# Mainboard.net
KiCad netlist of a schematic drawn in EAGLE
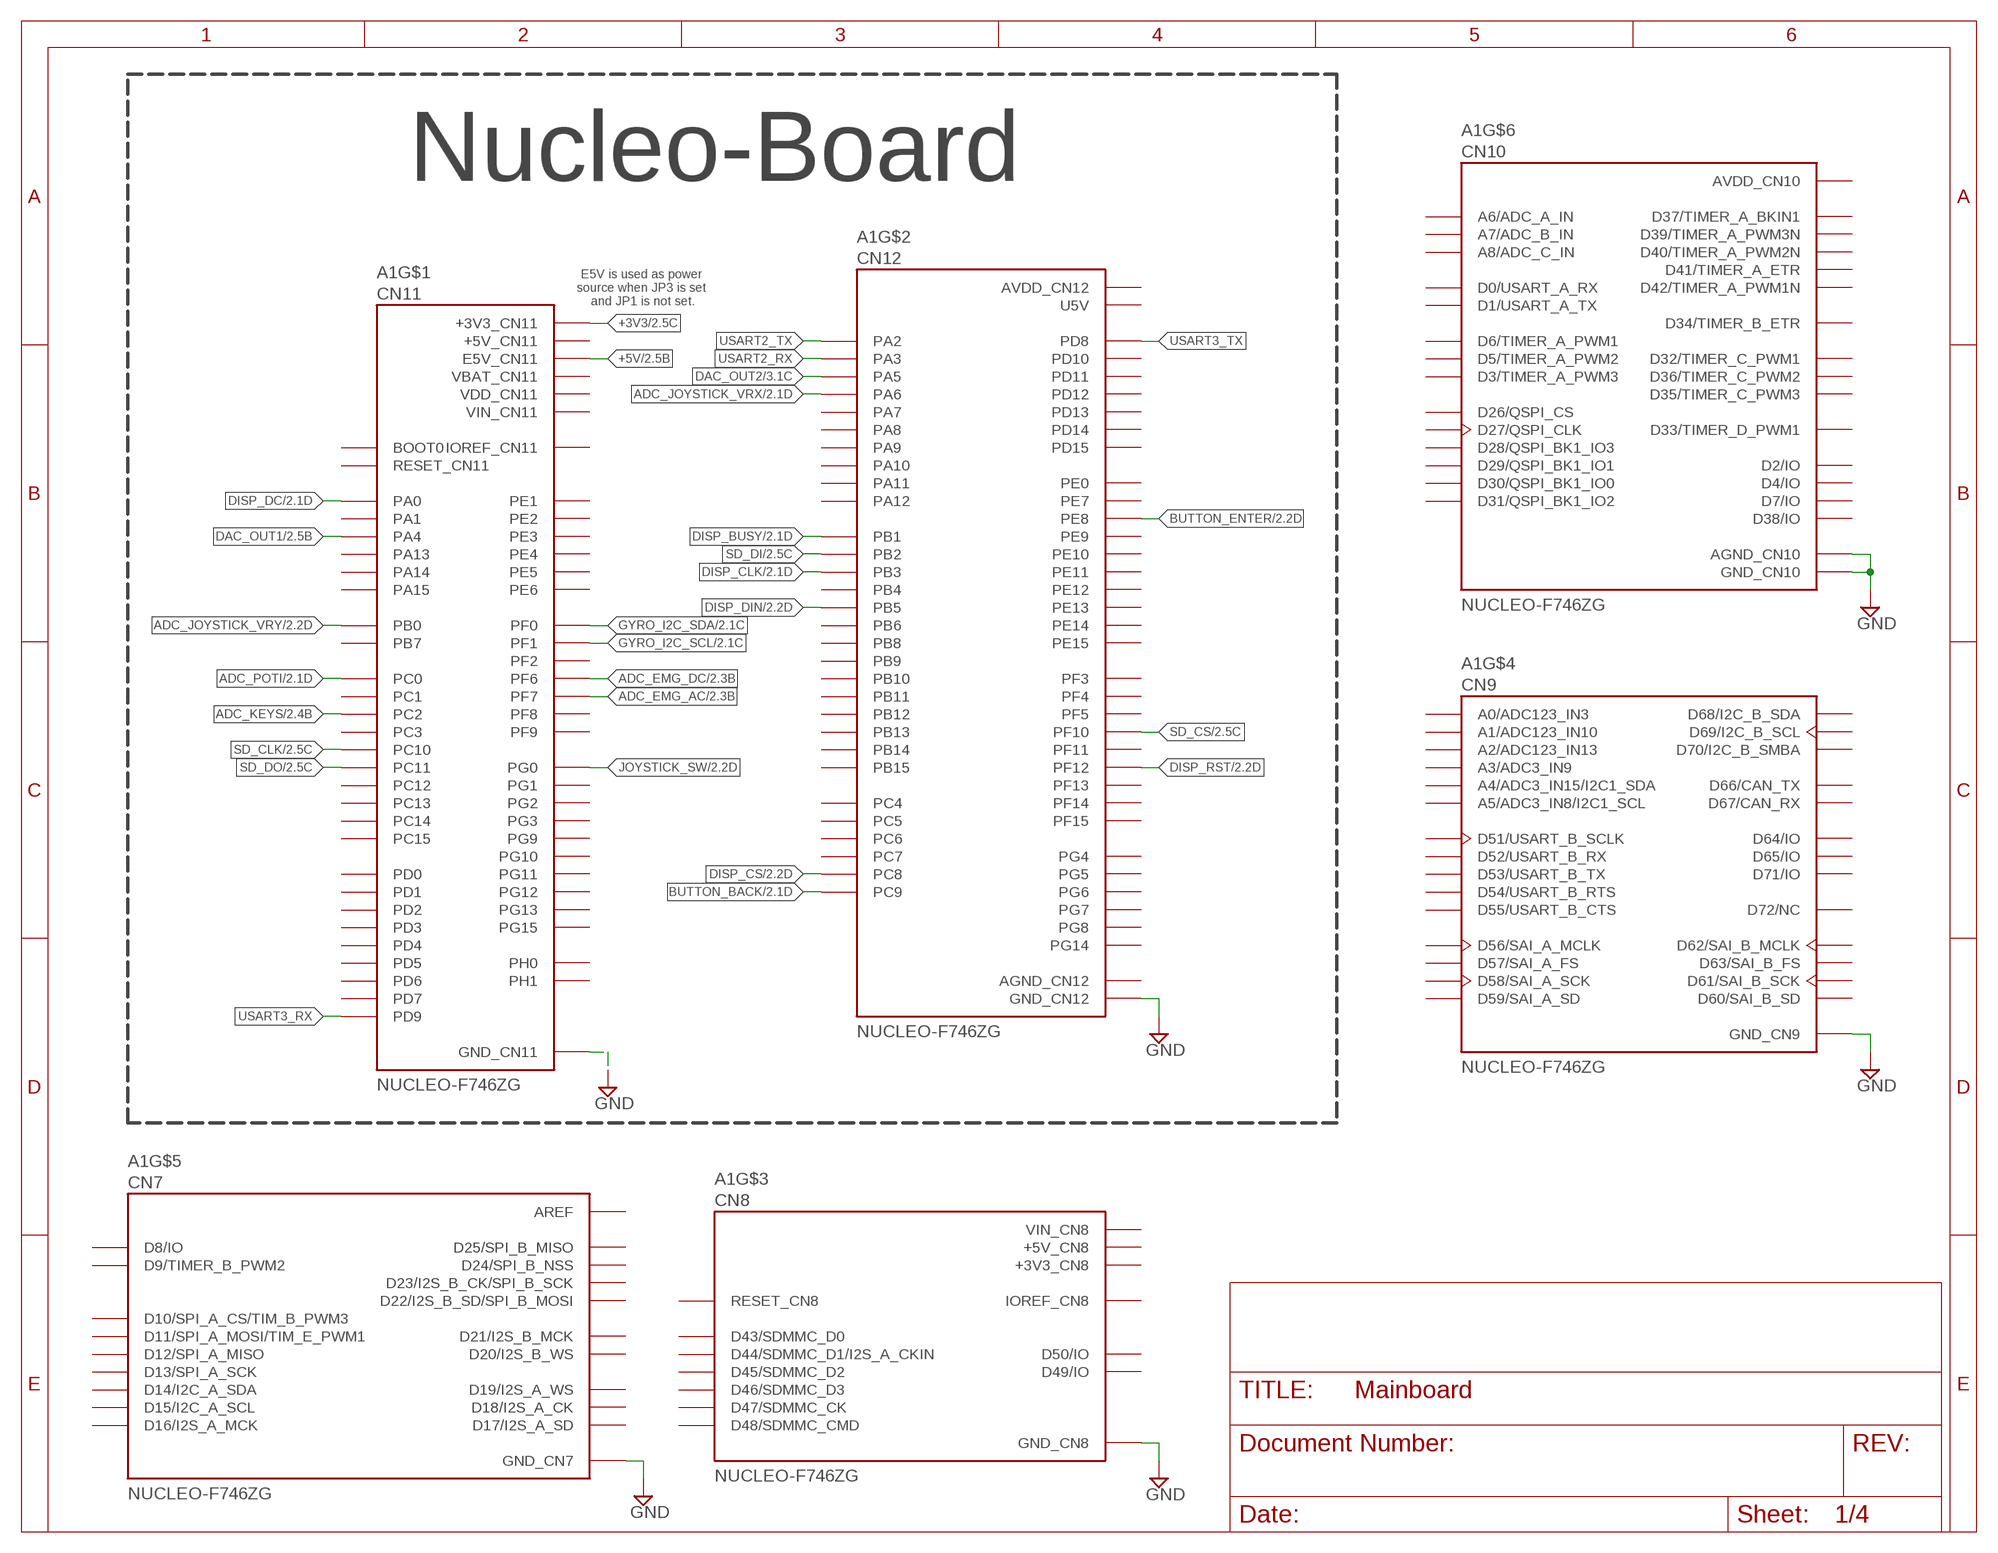
[diagram p0: schematic, sheet 1]
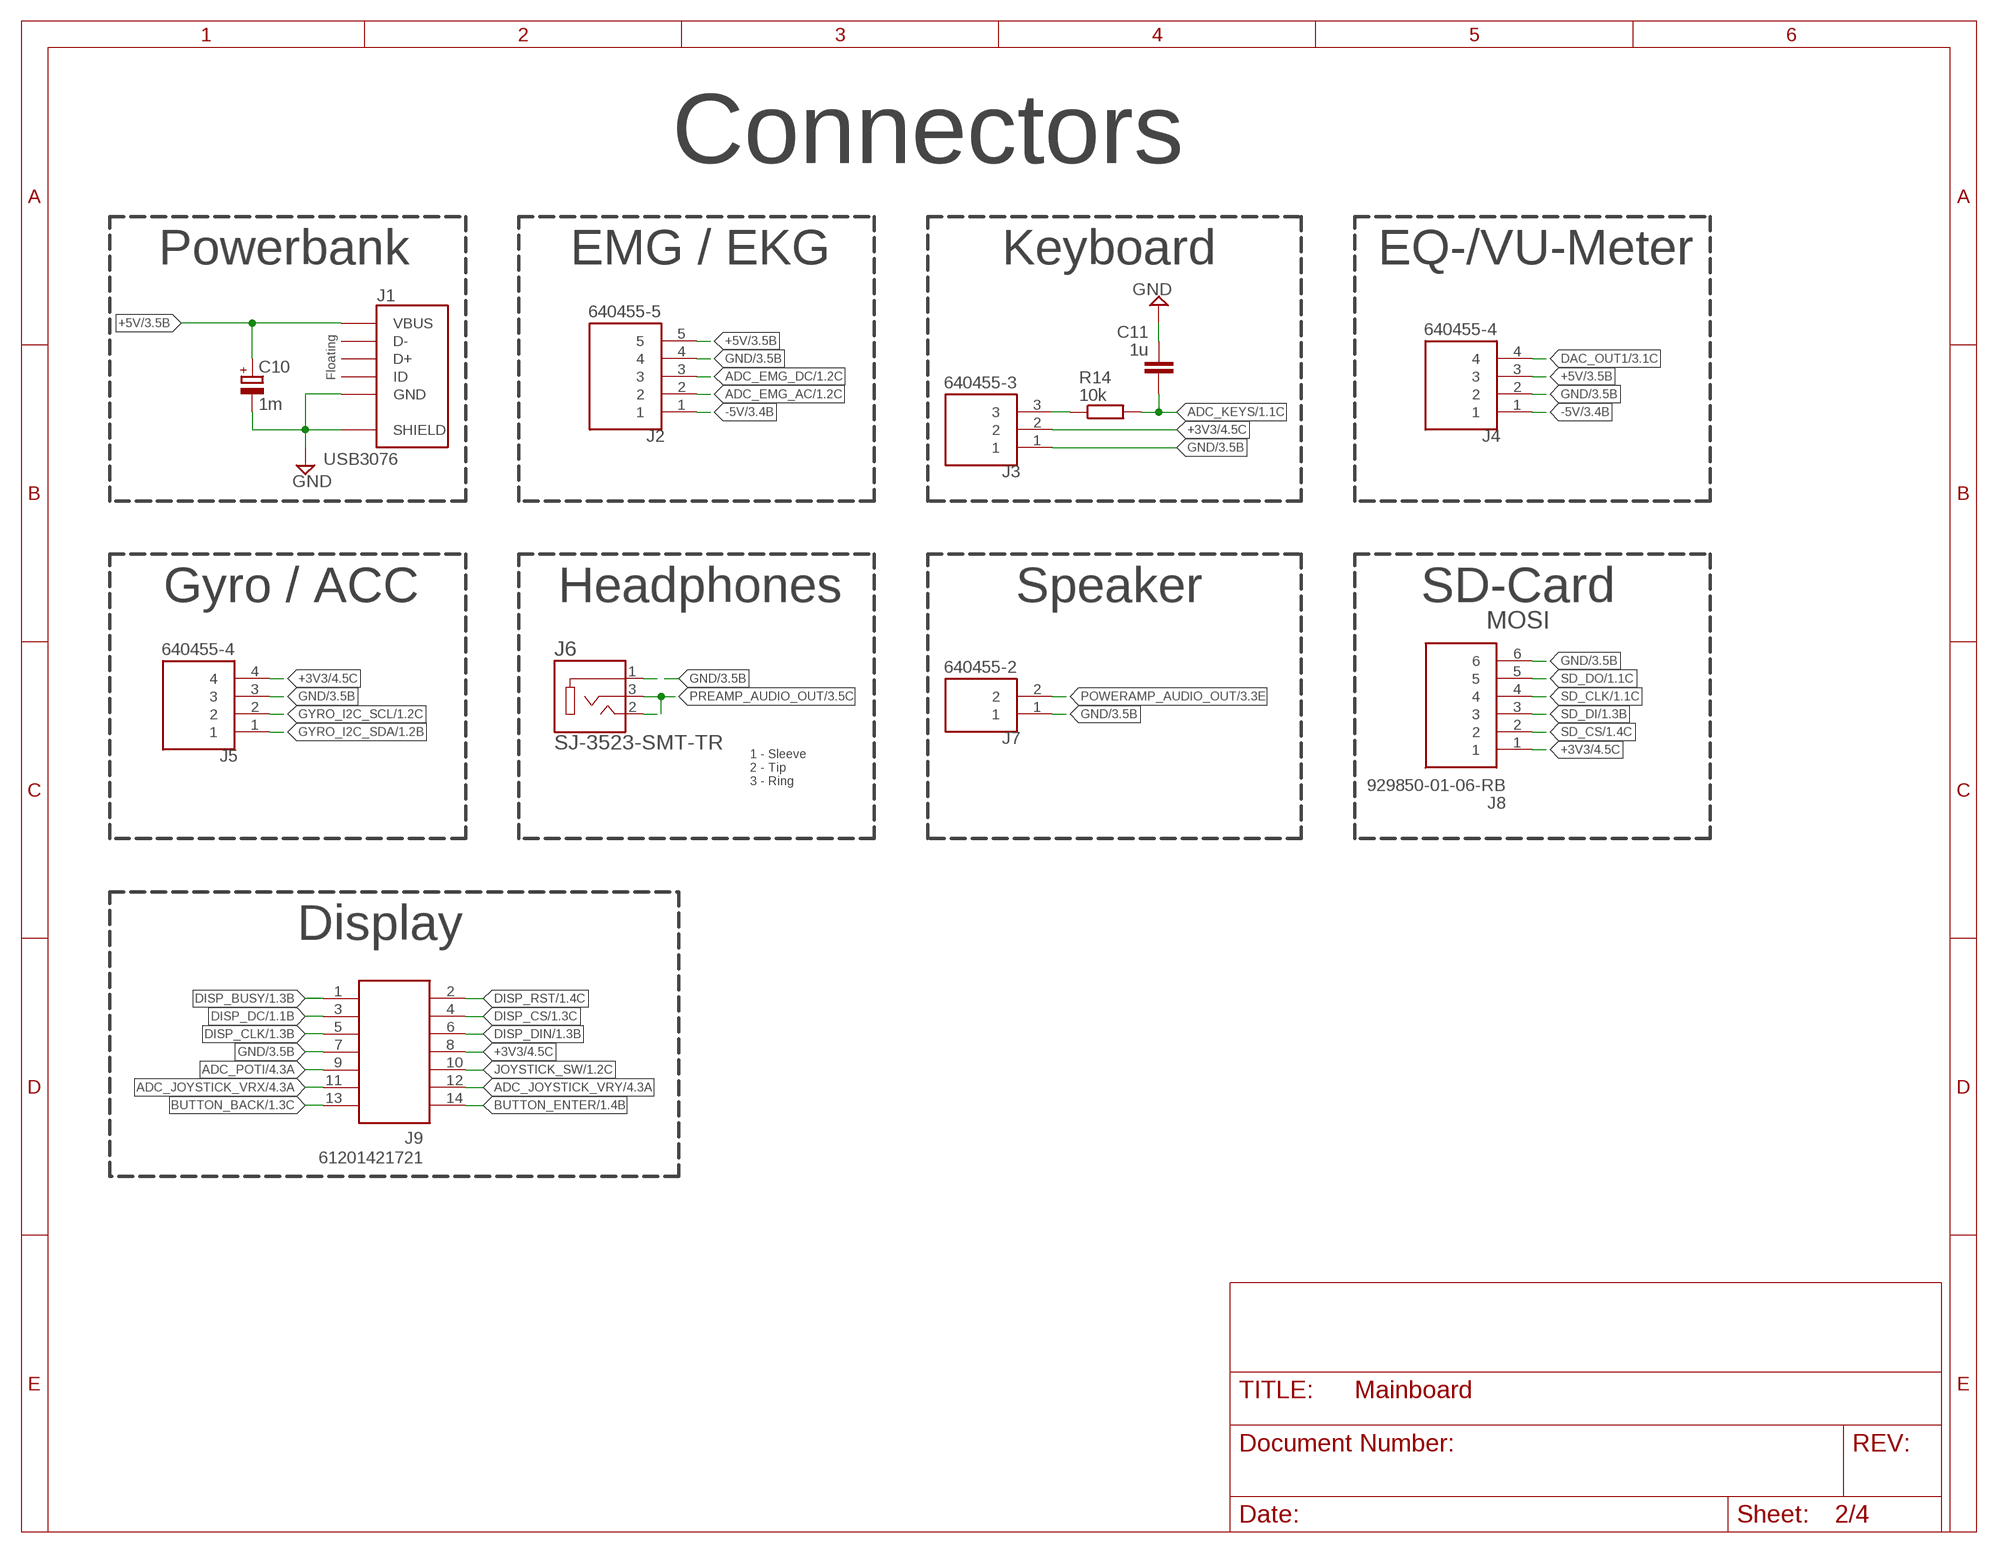
[diagram p1: schematic, sheet 2]
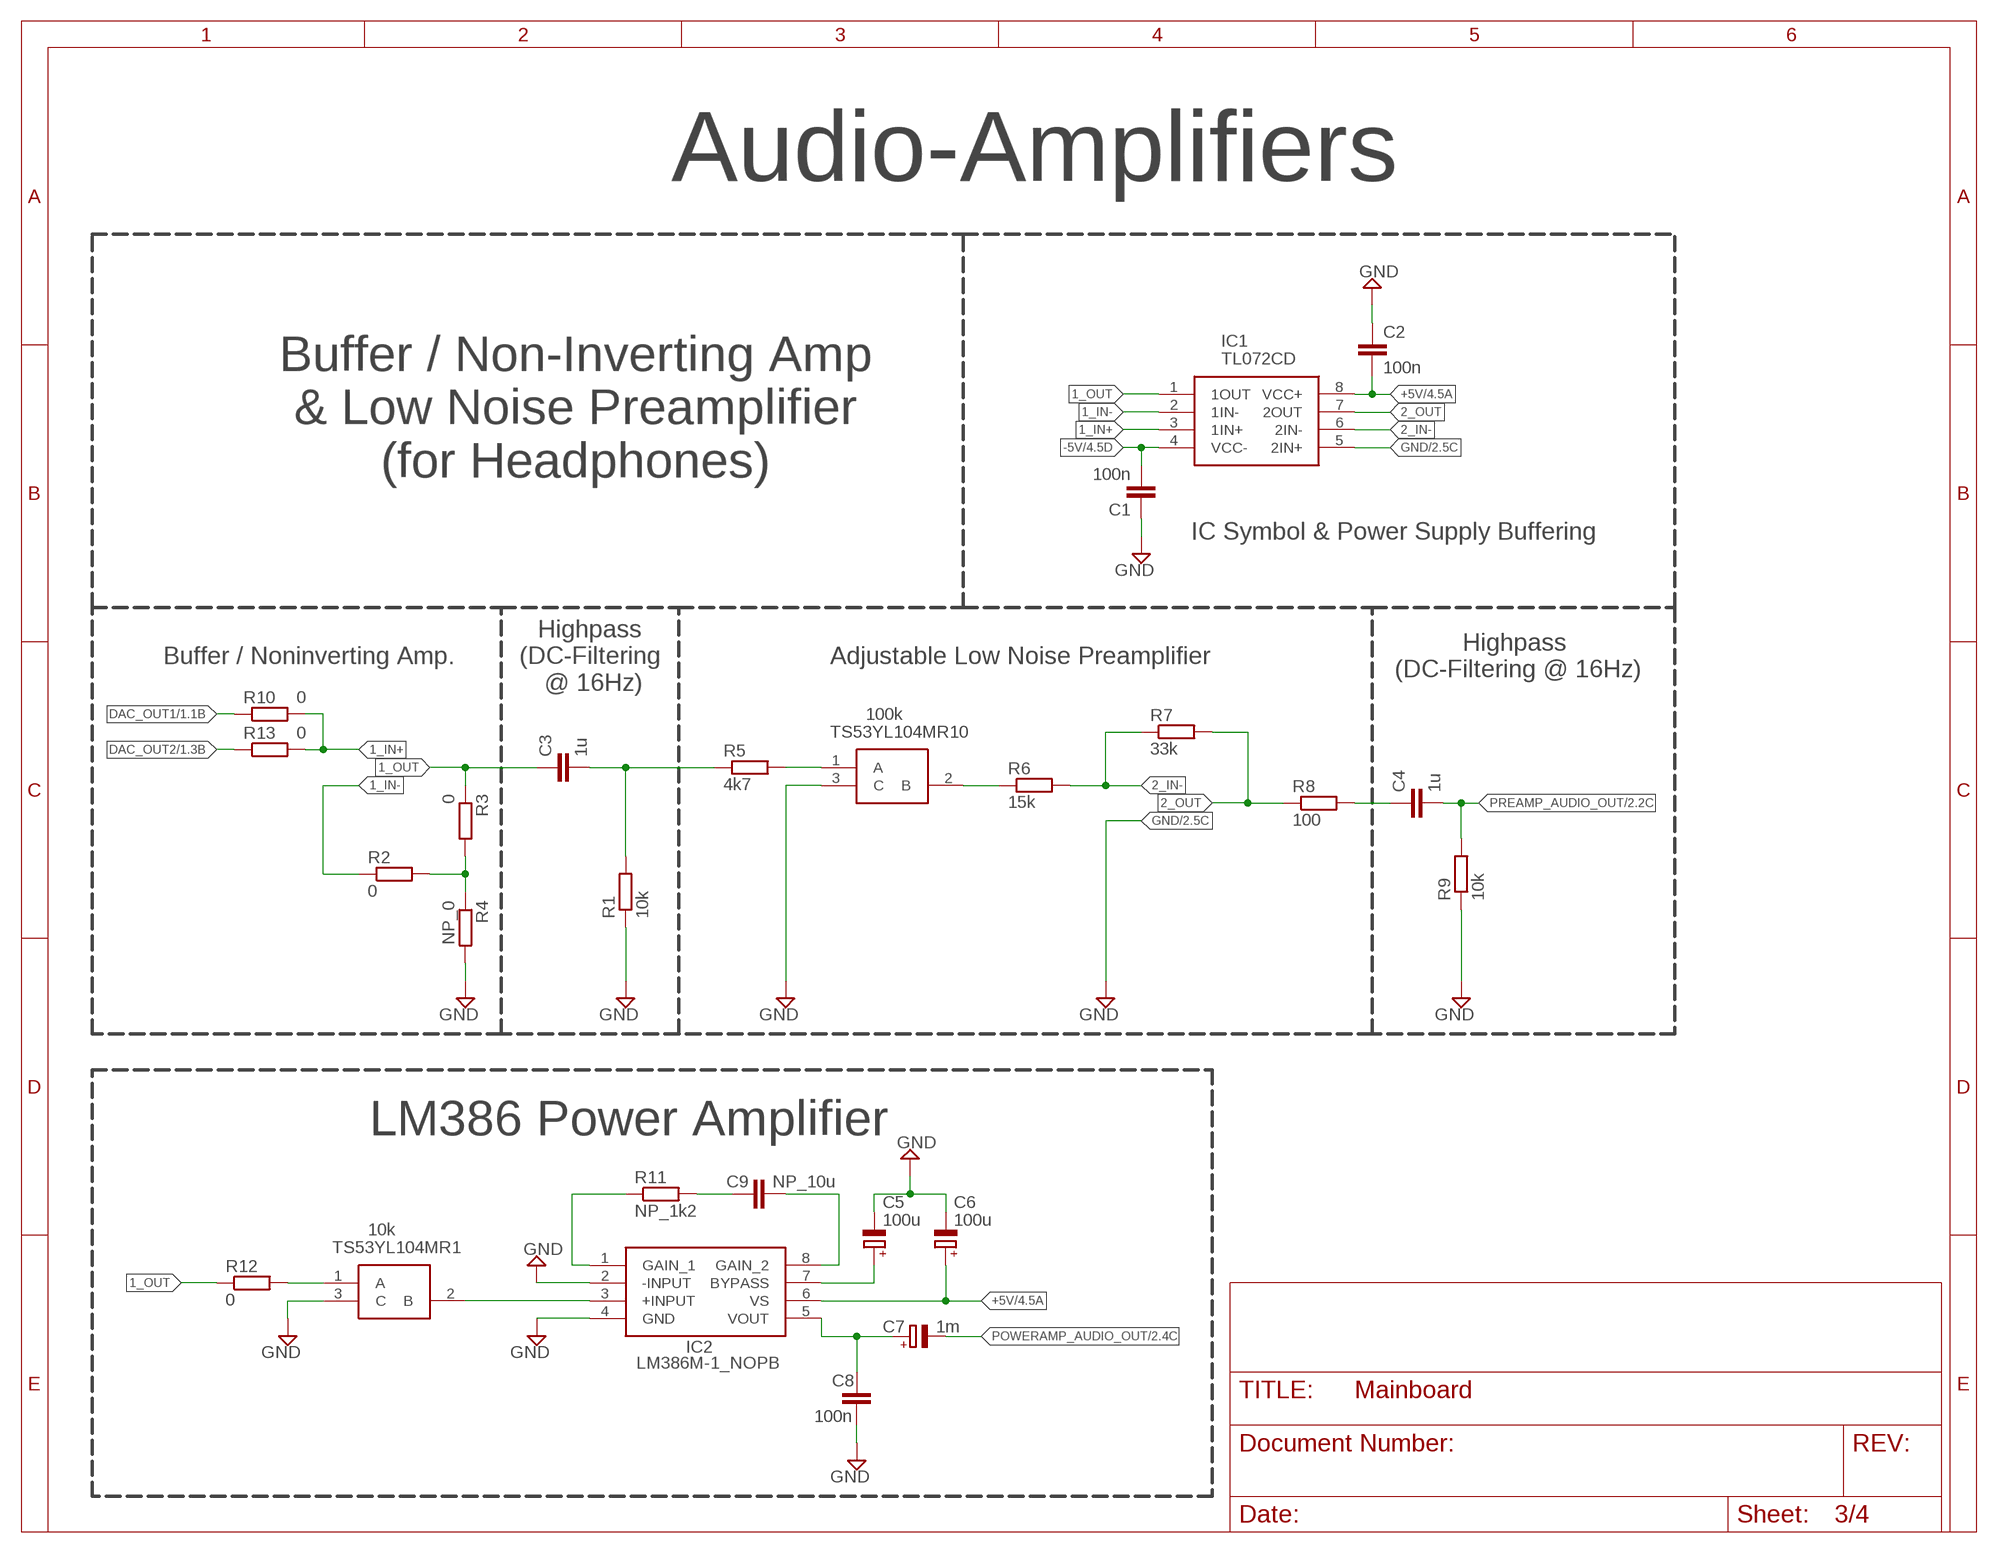
[diagram p2: schematic, sheet 3]
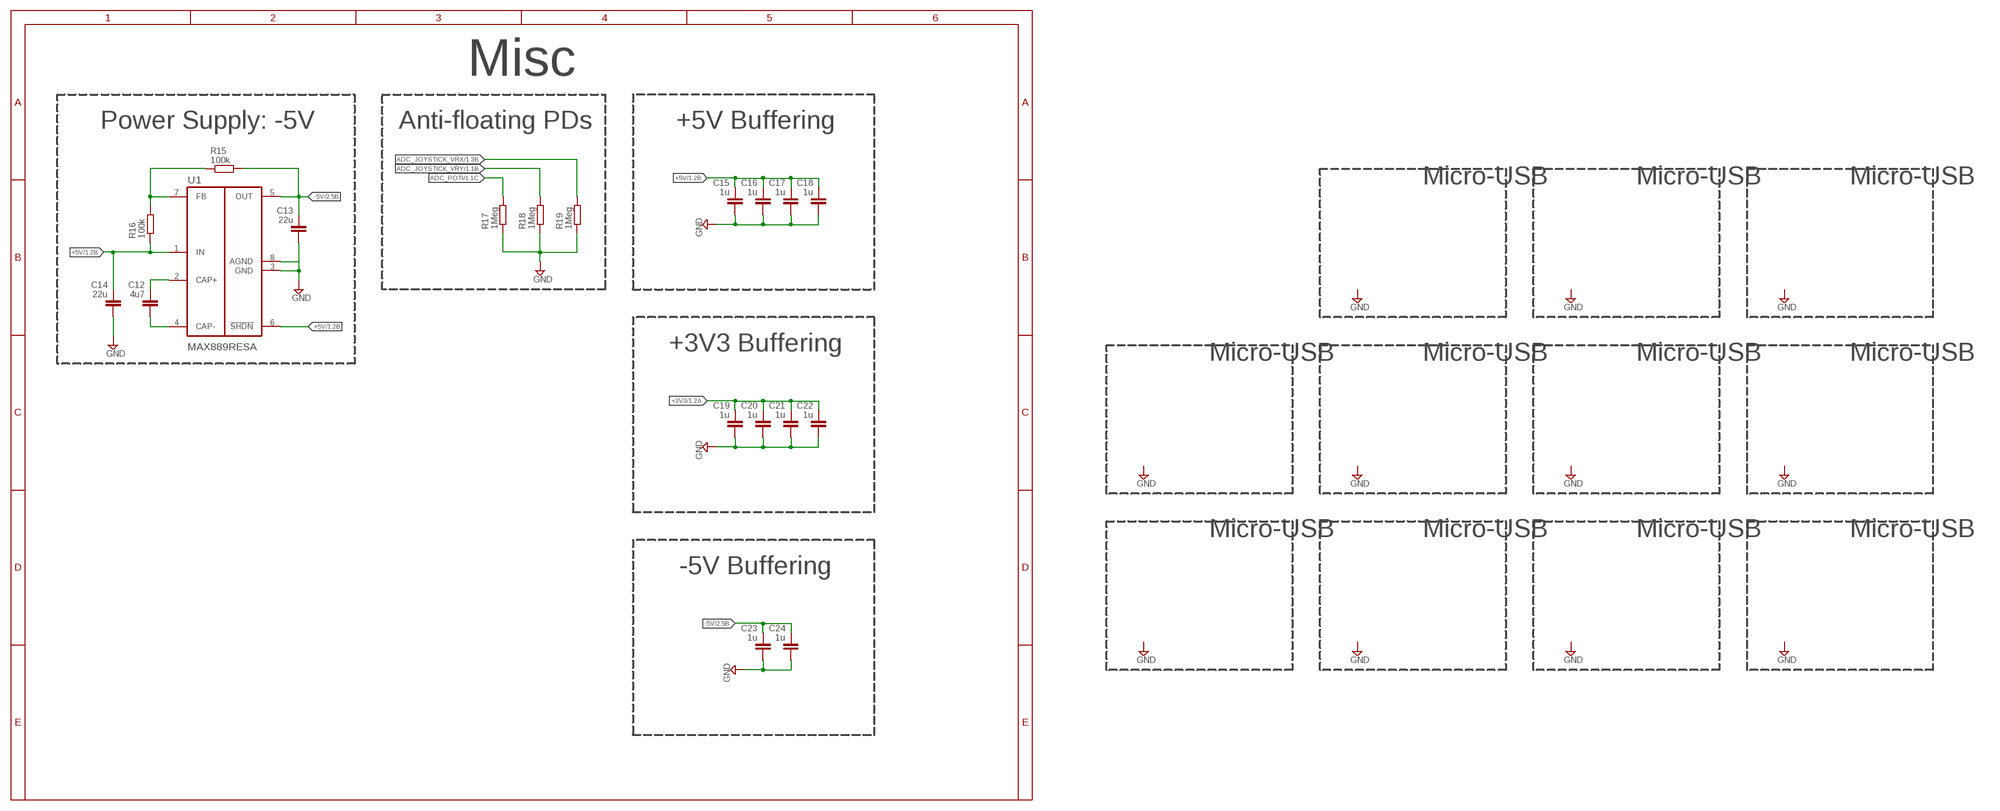
[diagram p3: schematic, sheet 4]

(export (version "E")
  (design (tool "Eeschema 10.0.6"))
  (components
    (comp (ref "C12")
      (value "4u7")
      (footprint "eagle-import:C0603")
      (libsource (lib "eagle-import") (part "C-EUC0603"))
    )
    (comp (ref "C13")
      (value "22u")
      (footprint "eagle-import:C0603")
      (libsource (lib "eagle-import") (part "C-EUC0603"))
    )
    (comp (ref "C14")
      (value "22u")
      (footprint "eagle-import:C0603")
      (libsource (lib "eagle-import") (part "C-EUC0603"))
    )
    (comp (ref "C15")
      (value "1u")
      (footprint "eagle-import:C0603")
      (libsource (lib "eagle-import") (part "C-EUC0603"))
    )
    (comp (ref "C16")
      (value "1u")
      (footprint "eagle-import:C0603")
      (libsource (lib "eagle-import") (part "C-EUC0603"))
    )
    (comp (ref "C17")
      (value "1u")
      (footprint "eagle-import:C0603")
      (libsource (lib "eagle-import") (part "C-EUC0603"))
    )
    (comp (ref "C18")
      (value "1u")
      (footprint "eagle-import:C0603")
      (libsource (lib "eagle-import") (part "C-EUC0603"))
    )
    (comp (ref "C19")
      (value "1u")
      (footprint "eagle-import:C0603")
      (libsource (lib "eagle-import") (part "C-EUC0603"))
    )
    (comp (ref "C20")
      (value "1u")
      (footprint "eagle-import:C0603")
      (libsource (lib "eagle-import") (part "C-EUC0603"))
    )
    (comp (ref "C21")
      (value "1u")
      (footprint "eagle-import:C0603")
      (libsource (lib "eagle-import") (part "C-EUC0603"))
    )
    (comp (ref "C22")
      (value "1u")
      (footprint "eagle-import:C0603")
      (libsource (lib "eagle-import") (part "C-EUC0603"))
    )
    (comp (ref "C23")
      (value "1u")
      (footprint "eagle-import:C0603")
      (libsource (lib "eagle-import") (part "C-EUC0603"))
    )
    (comp (ref "C24")
      (value "1u")
      (footprint "eagle-import:C0603")
      (libsource (lib "eagle-import") (part "C-EUC0603"))
    )
    (comp (ref "R15")
      (value "100k")
      (footprint "eagle-import:R0603")
      (libsource (lib "eagle-import") (part "R-EU_R0603"))
    )
    (comp (ref "R16")
      (value "100k")
      (footprint "eagle-import:R0603")
      (libsource (lib "eagle-import") (part "R-EU_R0603"))
    )
    (comp (ref "R17")
      (value "1Meg")
      (footprint "eagle-import:R0603")
      (libsource (lib "eagle-import") (part "R-EU_R0603"))
    )
    (comp (ref "R18")
      (value "1Meg")
      (footprint "eagle-import:R0603")
      (libsource (lib "eagle-import") (part "R-EU_R0603"))
    )
    (comp (ref "R19")
      (value "1Meg")
      (footprint "eagle-import:R0603")
      (libsource (lib "eagle-import") (part "R-EU_R0603"))
    )
    (comp (ref "U1")
      (value "MAX889RESA")
      (footprint "eagle-import:SOIC127P600X175-8N")
      (fields (field (name "MF") "Maxim Integrated") (field (name "MP") "MAX889RESA+"))
      (libsource (lib "eagle-import") (part "MAX889RESA"))
    )
    (comp (ref "C1")
      (value "100n")
      (footprint "eagle-import:C0603")
      (libsource (lib "eagle-import") (part "C-EUC0603"))
    )
    (comp (ref "C2")
      (value "100n")
      (footprint "eagle-import:C0603")
      (libsource (lib "eagle-import") (part "C-EUC0603"))
    )
    (comp (ref "C3")
      (value "1u")
      (footprint "eagle-import:C0603")
      (libsource (lib "eagle-import") (part "C-EUC0603"))
    )
    (comp (ref "C4")
      (value "1u")
      (footprint "eagle-import:C0603")
      (libsource (lib "eagle-import") (part "C-EUC0603"))
    )
    (comp (ref "C5")
      (value "100u")
      (footprint "eagle-import:E2,5-5")
      (libsource (lib "eagle-import") (part "CPOL-EUE2.5-5"))
    )
    (comp (ref "C6")
      (value "100u")
      (footprint "eagle-import:E2,5-5")
      (libsource (lib "eagle-import") (part "CPOL-EUE2.5-5"))
    )
    (comp (ref "C7")
      (value "1m")
      (footprint "eagle-import:E2,5-5")
      (libsource (lib "eagle-import") (part "CPOL-EUE2.5-5"))
    )
    (comp (ref "C8")
      (value "100n")
      (footprint "eagle-import:C0603")
      (libsource (lib "eagle-import") (part "C-EUC0603"))
    )
    (comp (ref "C9")
      (value "NP_10u")
      (footprint "eagle-import:C0603")
      (libsource (lib "eagle-import") (part "C-EUC0603"))
    )
    (comp (ref "IC1")
      (value "TL072CD")
      (footprint "eagle-import:SOIC127P600X175-8N")
      (fields (field (name "MOUSER_PART_NUMBER") "595-TL072CD"))
      (libsource (lib "eagle-import") (part "TL072CD"))
    )
    (comp (ref "IC2")
      (value "LM386M-1_NOPB")
      (footprint "eagle-import:SOIC127P600X175-8N")
      (fields
        (field (name "MANUFACTURER_PART_NUMBER") "LM386M-1/NOPB")
        (field (name "MOUSER_PART_NUMBER") "926-LM386M-1/NOPB")
      )
      (libsource (lib "eagle-import") (part "LM386M-1_NOPB"))
    )
    (comp (ref "R1")
      (value "10k")
      (footprint "eagle-import:R0603")
      (libsource (lib "eagle-import") (part "R-EU_R0603"))
    )
    (comp (ref "R2")
      (value "0")
      (footprint "eagle-import:R0603")
      (libsource (lib "eagle-import") (part "R-EU_R0603"))
    )
    (comp (ref "R3")
      (value "0")
      (footprint "eagle-import:R0603")
      (libsource (lib "eagle-import") (part "R-EU_R0603"))
    )
    (comp (ref "R4")
      (value "NP_0")
      (footprint "eagle-import:R0603")
      (libsource (lib "eagle-import") (part "R-EU_R0603"))
    )
    (comp (ref "R5")
      (value "4k7")
      (footprint "eagle-import:R0603")
      (libsource (lib "eagle-import") (part "R-EU_R0603"))
    )
    (comp (ref "R6")
      (value "15k")
      (footprint "eagle-import:R0603")
      (libsource (lib "eagle-import") (part "R-EU_R0603"))
    )
    (comp (ref "R7")
      (value "33k")
      (footprint "eagle-import:R0603")
      (libsource (lib "eagle-import") (part "R-EU_R0603"))
    )
    (comp (ref "R8")
      (value "100")
      (footprint "eagle-import:R0603")
      (libsource (lib "eagle-import") (part "R-EU_R0603"))
    )
    (comp (ref "R9")
      (value "10k")
      (footprint "eagle-import:R0603")
      (libsource (lib "eagle-import") (part "R-EU_R0603"))
    )
    (comp (ref "R10")
      (value "0")
      (footprint "eagle-import:R0603")
      (libsource (lib "eagle-import") (part "R-EU_R0603"))
    )
    (comp (ref "R11")
      (value "NP_1k2")
      (footprint "eagle-import:R0603")
      (libsource (lib "eagle-import") (part "R-EU_R0603"))
    )
    (comp (ref "R12")
      (value "0")
      (footprint "eagle-import:R0603")
      (libsource (lib "eagle-import") (part "R-EU_R0603"))
    )
    (comp (ref "R13")
      (value "0")
      (footprint "eagle-import:R0603")
      (libsource (lib "eagle-import") (part "R-EU_R0603"))
    )
    (comp (ref "TS53YL104MR1")
      (value "10k")
      (footprint "eagle-import:TS53YL203MR10")
      (fields
        (field (name "MANUFACTURER_PART_NUMBER") "TS53YL203MR10")
        (field (name "MOUSER_PART_NUMBER") "72-TS53YL-20K")
      )
      (libsource (lib "eagle-import") (part "TS53YL203MR10"))
    )
    (comp (ref "TS53YL104MR10")
      (value "100k")
      (footprint "eagle-import:TS53YL203MR10")
      (fields
        (field (name "MANUFACTURER_PART_NUMBER") "TS53YL203MR10")
        (field (name "MOUSER_PART_NUMBER") "72-TS53YL-20K")
      )
      (libsource (lib "eagle-import") (part "TS53YL203MR10"))
    )
    (comp (ref "A1")
      (value "NUCLEO-F746ZG")
      (footprint "eagle-import:MODULE_NUCLEO-F746ZG")
      (fields (field (name "MF") "STMicroelectronics"))
      (libsource (lib "eagle-import") (part "NUCLEO-F746ZG"))
    )
    (comp (ref "C10")
      (value "1m")
      (footprint "eagle-import:E2,5-5")
      (libsource (lib "eagle-import") (part "CPOL-EUE2.5-5"))
    )
    (comp (ref "C11")
      (value "1u")
      (footprint "eagle-import:C0603")
      (libsource (lib "eagle-import") (part "C-EUC0603"))
    )
    (comp (ref "J1")
      (value "USB3076")
      (footprint "eagle-import:GCT_USB3076-XX-X_REVC")
      (fields (field (name "MF") "Global Connector Technology") (field (name "MP") "USB3076-30-A"))
      (libsource (lib "eagle-import") (part "USB3076-XX-X_REVC"))
    )
    (comp (ref "J2")
      (value "640455-5")
      (footprint "eagle-import:TE_640455-5")
      (fields (field (name "DIGI-KEY_PART_NUMBER") "A19453-ND") (field (name "MF") "TE Connectivity"))
      (libsource (lib "eagle-import") (part "640455-5"))
    )
    (comp (ref "J3")
      (value "640455-3")
      (footprint "eagle-import:TE_640455-3")
      (fields (field (name "MF") "TE Connectivity"))
      (libsource (lib "eagle-import") (part "640455-3"))
    )
    (comp (ref "J4")
      (value "640455-4")
      (footprint "eagle-import:TE_640455-4")
      (fields (field (name "MF") "TE Connectivity"))
      (libsource (lib "eagle-import") (part "640455-4"))
    )
    (comp (ref "J5")
      (value "640455-4")
      (footprint "eagle-import:TE_640455-4")
      (fields (field (name "MF") "TE Connectivity"))
      (libsource (lib "eagle-import") (part "640455-4"))
    )
    (comp (ref "J6")
      (value "SJ-3523-SMT-TR")
      (footprint "eagle-import:CUI_SJ-3523-SMT-TR")
      (fields (field (name "MF") "CUI Devices"))
      (libsource (lib "eagle-import") (part "SJ-3523-SMT-TR"))
    )
    (comp (ref "J7")
      (value "640455-2")
      (footprint "eagle-import:TE_640455-2")
      (fields (field (name "MF") "TE Connectivity"))
      (libsource (lib "eagle-import") (part "640455-2"))
    )
    (comp (ref "J8")
      (value "929850-01-06-RB")
      (footprint "eagle-import:RHDR6W76P0X254_1X6_1524X254X82")
      (fields (field (name "MOUSER_PART_NUMBER") "517-929850-01-06-RB"))
      (libsource (lib "eagle-import") (part "929850-01-06-RB"))
    )
    (comp (ref "J9")
      (value "61201421721")
      (footprint "eagle-import:61201421721")
      (fields (field (name "MF") "Würth Elektronik"))
      (libsource (lib "eagle-import") (part "61201421721"))
    )
    (comp (ref "R14")
      (value "10k")
      (footprint "eagle-import:R0603")
      (libsource (lib "eagle-import") (part "R-EU_R0603"))
    )
  )
  (nets
    (net (code "1") (name "+3V3") (class "Default")
      (node (ref "A1") (pin "CN11_16") (pinfunction "+3V3_CN11_CN11_16") (pintype "power_in"))
      (node (ref "C19") (pin "2") (pinfunction "2_2") (pintype "passive"))
      (node (ref "C20") (pin "2") (pinfunction "2_2") (pintype "passive"))
      (node (ref "C21") (pin "2") (pinfunction "2_2") (pintype "passive"))
      (node (ref "C22") (pin "2") (pinfunction "2_2") (pintype "passive"))
      (node (ref "J3") (pin "2") (pinfunction "2_2") (pintype "passive"))
      (node (ref "J5") (pin "4") (pinfunction "4_4") (pintype "passive"))
      (node (ref "J8") (pin "1") (pinfunction "1_1") (pintype "bidirectional"))
      (node (ref "J9") (pin "8") (pinfunction "8_8") (pintype "passive"))
    )
    (net (code "2") (name "+3V3_CN8") (class "Default")
      (node (ref "A1") (pin "CN8_7") (pinfunction "+3V3_CN8_CN8_7") (pintype "power_in"))
    )
    (net (code "3") (name "+5V") (class "Default")
      (node (ref "A1") (pin "CN11_6") (pinfunction "E5V_CN11_CN11_6") (pintype "power_in"))
      (node (ref "C10") (pin "+") (pinfunction "+_+") (pintype "passive"))
      (node (ref "C14") (pin "2") (pinfunction "2_2") (pintype "passive"))
      (node (ref "C15") (pin "2") (pinfunction "2_2") (pintype "passive"))
      (node (ref "C16") (pin "2") (pinfunction "2_2") (pintype "passive"))
      (node (ref "C17") (pin "2") (pinfunction "2_2") (pintype "passive"))
      (node (ref "C18") (pin "2") (pinfunction "2_2") (pintype "passive"))
      (node (ref "C2") (pin "2") (pinfunction "2_2") (pintype "passive"))
      (node (ref "C6") (pin "+") (pinfunction "+_+") (pintype "passive"))
      (node (ref "IC1") (pin "8") (pinfunction "VCC+_8") (pintype "power_in"))
      (node (ref "IC2") (pin "6") (pinfunction "VS_6") (pintype "bidirectional"))
      (node (ref "J1") (pin "1") (pinfunction "VBUS_1") (pintype "power_in"))
      (node (ref "J2") (pin "5") (pinfunction "5_5") (pintype "passive"))
      (node (ref "J4") (pin "3") (pinfunction "3_3") (pintype "passive"))
      (node (ref "R16") (pin "1") (pinfunction "1_1") (pintype "passive"))
      (node (ref "U1") (pin "1") (pinfunction "IN_1") (pintype "input"))
      (node (ref "U1") (pin "6") (pinfunction "~{SHDN}_6") (pintype "input"))
    )
    (net (code "4") (name "+5V_CN8") (class "Default")
      (node (ref "A1") (pin "CN8_9") (pinfunction "+5V_CN8_CN8_9") (pintype "power_in"))
    )
    (net (code "5") (name "+5V_CN11") (class "Default")
      (node (ref "A1") (pin "CN11_18") (pinfunction "+5V_CN11_CN11_18") (pintype "power_in"))
    )
    (net (code "6") (name "-5V") (class "Default")
      (node (ref "C1") (pin "2") (pinfunction "2_2") (pintype "passive"))
      (node (ref "C13") (pin "2") (pinfunction "2_2") (pintype "passive"))
      (node (ref "C23") (pin "2") (pinfunction "2_2") (pintype "passive"))
      (node (ref "C24") (pin "2") (pinfunction "2_2") (pintype "passive"))
      (node (ref "IC1") (pin "4") (pinfunction "VCC-_4") (pintype "power_in"))
      (node (ref "J2") (pin "1") (pinfunction "1_1") (pintype "passive"))
      (node (ref "J4") (pin "1") (pinfunction "1_1") (pintype "passive"))
      (node (ref "R15") (pin "2") (pinfunction "2_2") (pintype "passive"))
      (node (ref "U1") (pin "5") (pinfunction "OUT_5") (pintype "output"))
    )
    (net (code "7") (name "1_IN+") (class "Default")
      (node (ref "IC1") (pin "3") (pinfunction "1IN+_3") (pintype "input"))
      (node (ref "R10") (pin "2") (pinfunction "2_2") (pintype "passive"))
      (node (ref "R13") (pin "2") (pinfunction "2_2") (pintype "passive"))
    )
    (net (code "8") (name "1_IN-") (class "Default")
      (node (ref "IC1") (pin "2") (pinfunction "1IN-_2") (pintype "input"))
      (node (ref "R2") (pin "1") (pinfunction "1_1") (pintype "passive"))
    )
    (net (code "9") (name "1_OUT") (class "Default")
      (node (ref "C3") (pin "1") (pinfunction "1_1") (pintype "passive"))
      (node (ref "IC1") (pin "1") (pinfunction "1OUT_1") (pintype "output"))
      (node (ref "R12") (pin "1") (pinfunction "1_1") (pintype "passive"))
      (node (ref "R3") (pin "1") (pinfunction "1_1") (pintype "passive"))
    )
    (net (code "10") (name "2_IN-") (class "Default")
      (node (ref "IC1") (pin "6") (pinfunction "2IN-_6") (pintype "input"))
      (node (ref "R6") (pin "2") (pinfunction "2_2") (pintype "passive"))
      (node (ref "R7") (pin "1") (pinfunction "1_1") (pintype "passive"))
    )
    (net (code "11") (name "2_OUT") (class "Default")
      (node (ref "IC1") (pin "7") (pinfunction "2OUT_7") (pintype "output"))
      (node (ref "R7") (pin "2") (pinfunction "2_2") (pintype "passive"))
      (node (ref "R8") (pin "1") (pinfunction "1_1") (pintype "passive"))
    )
    (net (code "12") (name "ADC_EMG_AC") (class "Default")
      (node (ref "A1") (pin "CN11_11") (pinfunction "PF7_CN11_11") (pintype "bidirectional"))
      (node (ref "J2") (pin "2") (pinfunction "2_2") (pintype "passive"))
    )
    (net (code "13") (name "ADC_EMG_DC") (class "Default")
      (node (ref "A1") (pin "CN11_9") (pinfunction "PF6_CN11_9") (pintype "bidirectional"))
      (node (ref "J2") (pin "3") (pinfunction "3_3") (pintype "passive"))
    )
    (net (code "14") (name "ADC_JOYSTICK_VRX") (class "Default")
      (node (ref "A1") (pin "CN12_13") (pinfunction "PA6_CN12_13") (pintype "bidirectional"))
      (node (ref "J9") (pin "11") (pinfunction "11_11") (pintype "passive"))
      (node (ref "R19") (pin "2") (pinfunction "2_2") (pintype "passive"))
    )
    (net (code "15") (name "ADC_JOYSTICK_VRY") (class "Default")
      (node (ref "A1") (pin "CN11_34") (pinfunction "PB0_CN11_34") (pintype "bidirectional"))
      (node (ref "J9") (pin "12") (pinfunction "12_12") (pintype "passive"))
      (node (ref "R18") (pin "2") (pinfunction "2_2") (pintype "passive"))
    )
    (net (code "16") (name "ADC_KEYS") (class "Default")
      (node (ref "A1") (pin "CN11_35") (pinfunction "PC2_CN11_35") (pintype "bidirectional"))
      (node (ref "C11") (pin "1") (pinfunction "1_1") (pintype "passive"))
      (node (ref "R14") (pin "2") (pinfunction "2_2") (pintype "passive"))
    )
    (net (code "17") (name "ADC_POTI") (class "Default")
      (node (ref "A1") (pin "CN11_38") (pinfunction "PC0_CN11_38") (pintype "bidirectional"))
      (node (ref "J9") (pin "9") (pinfunction "9_9") (pintype "passive"))
      (node (ref "R17") (pin "2") (pinfunction "2_2") (pintype "passive"))
    )
    (net (code "18") (name "AGND_CN12") (class "Default")
      (node (ref "A1") (pin "CN12_32") (pinfunction "AGND_CN12_CN12_32") (pintype "power_in"))
    )
    (net (code "19") (name "AREF") (class "Default")
      (node (ref "A1") (pin "CN7_6") (pinfunction "AREF_CN7_6") (pintype "power_in"))
    )
    (net (code "20") (name "AVDD_CN10") (class "Default")
      (node (ref "A1") (pin "CN10_1") (pinfunction "AVDD_CN10_CN10_1") (pintype "power_in"))
    )
    (net (code "21") (name "AVDD_CN12") (class "Default")
      (node (ref "A1") (pin "CN12_7") (pinfunction "AVDD_CN12_CN12_7") (pintype "power_in"))
    )
    (net (code "22") (name "BUTTON_BACK") (class "Default")
      (node (ref "A1") (pin "CN12_1") (pinfunction "PC9_CN12_1") (pintype "bidirectional"))
      (node (ref "J9") (pin "13") (pinfunction "13_13") (pintype "passive"))
    )
    (net (code "23") (name "BUTTON_ENTER") (class "Default")
      (node (ref "A1") (pin "CN12_40") (pinfunction "PE8_CN12_40") (pintype "bidirectional"))
      (node (ref "J9") (pin "14") (pinfunction "14_14") (pintype "passive"))
    )
    (net (code "24") (name "DAC_OUT1") (class "Default")
      (node (ref "A1") (pin "CN11_32") (pinfunction "PA4_CN11_32") (pintype "bidirectional"))
      (node (ref "J4") (pin "4") (pinfunction "4_4") (pintype "passive"))
      (node (ref "R10") (pin "1") (pinfunction "1_1") (pintype "passive"))
    )
    (net (code "25") (name "DAC_OUT2") (class "Default")
      (node (ref "A1") (pin "CN12_11") (pinfunction "PA5_CN12_11") (pintype "bidirectional"))
      (node (ref "R13") (pin "1") (pinfunction "1_1") (pintype "passive"))
    )
    (net (code "26") (name "DISP_BUSY") (class "Default")
      (node (ref "A1") (pin "CN12_24") (pinfunction "PB1_CN12_24") (pintype "bidirectional"))
      (node (ref "J9") (pin "1") (pinfunction "1_1") (pintype "passive"))
    )
    (net (code "27") (name "DISP_CLK") (class "Default")
      (node (ref "A1") (pin "CN12_31") (pinfunction "PB3_CN12_31") (pintype "bidirectional"))
      (node (ref "J9") (pin "5") (pinfunction "5_5") (pintype "passive"))
    )
    (net (code "28") (name "DISP_CS") (class "Default")
      (node (ref "A1") (pin "CN12_2") (pinfunction "PC8_CN12_2") (pintype "bidirectional"))
      (node (ref "J9") (pin "4") (pinfunction "4_4") (pintype "passive"))
    )
    (net (code "29") (name "DISP_DC") (class "Default")
      (node (ref "A1") (pin "CN11_28") (pinfunction "PA0_CN11_28") (pintype "bidirectional"))
      (node (ref "J9") (pin "3") (pinfunction "3_3") (pintype "passive"))
    )
    (net (code "30") (name "DISP_DIN") (class "Default")
      (node (ref "A1") (pin "CN12_29") (pinfunction "PB5_CN12_29") (pintype "bidirectional"))
      (node (ref "J9") (pin "6") (pinfunction "6_6") (pintype "passive"))
    )
    (net (code "31") (name "DISP_RST") (class "Default")
      (node (ref "A1") (pin "CN12_59") (pinfunction "PF12_CN12_59") (pintype "bidirectional"))
      (node (ref "J9") (pin "2") (pinfunction "2_2") (pintype "passive"))
    )
    (net (code "32") (name "GND") (class "Default")
      (node (ref "A1") (pin "CN10_17") (pinfunction "GND_CN10_CN10_17") (pintype "power_in"))
      (node (ref "A1") (pin "CN10_22") (pinfunction "GND_CN10_CN10_22") (pintype "power_in"))
      (node (ref "A1") (pin "CN10_27") (pinfunction "GND_CN10_CN10_27") (pintype "power_in"))
      (node (ref "A1") (pin "CN10_3") (pinfunction "AGND_CN10_CN10_3") (pintype "power_in"))
      (node (ref "A1") (pin "CN10_5") (pinfunction "GND_CN10_CN10_5") (pintype "power_in"))
      (node (ref "A1") (pin "CN11_19") (pinfunction "GND_CN11_CN11_19") (pintype "power_in"))
      (node (ref "A1") (pin "CN11_20") (pinfunction "GND_CN11_CN11_20") (pintype "power_in"))
      (node (ref "A1") (pin "CN11_22") (pinfunction "GND_CN11_CN11_22") (pintype "power_in"))
      (node (ref "A1") (pin "CN11_49") (pinfunction "GND_CN11_CN11_49") (pintype "power_in"))
      (node (ref "A1") (pin "CN11_60") (pinfunction "GND_CN11_CN11_60") (pintype "power_in"))
      (node (ref "A1") (pin "CN11_71") (pinfunction "GND_CN11_CN11_71") (pintype "power_in"))
      (node (ref "A1") (pin "CN11_72") (pinfunction "GND_CN11_CN11_72") (pintype "power_in"))
      (node (ref "A1") (pin "CN11_8") (pinfunction "GND_CN11_CN11_8") (pintype "power_in"))
      (node (ref "A1") (pin "CN12_20") (pinfunction "GND_CN12_CN12_20") (pintype "power_in"))
      (node (ref "A1") (pin "CN12_39") (pinfunction "GND_CN12_CN12_39") (pintype "power_in"))
      (node (ref "A1") (pin "CN12_54") (pinfunction "GND_CN12_CN12_54") (pintype "power_in"))
      (node (ref "A1") (pin "CN12_63") (pinfunction "GND_CN12_CN12_63") (pintype "power_in"))
      (node (ref "A1") (pin "CN12_71") (pinfunction "GND_CN12_CN12_71") (pintype "power_in"))
      (node (ref "A1") (pin "CN12_72") (pinfunction "GND_CN12_CN12_72") (pintype "power_in"))
      (node (ref "A1") (pin "CN12_9") (pinfunction "GND_CN12_CN12_9") (pintype "power_in"))
      (node (ref "A1") (pin "CN7_8") (pinfunction "GND_CN7_CN7_8") (pintype "power_in"))
      (node (ref "A1") (pin "CN8_11") (pinfunction "GND_CN8_CN8_11") (pintype "power_in"))
      (node (ref "A1") (pin "CN8_13") (pinfunction "GND_CN8_CN8_13") (pintype "power_in"))
      (node (ref "A1") (pin "CN9_12") (pinfunction "GND_CN9_CN9_12") (pintype "power_in"))
      (node (ref "A1") (pin "CN9_23") (pinfunction "GND_CN9_CN9_23") (pintype "power_in"))
      (node (ref "C1") (pin "1") (pinfunction "1_1") (pintype "passive"))
      (node (ref "C10") (pin "-") (pinfunction "-_-") (pintype "passive"))
      (node (ref "C11") (pin "2") (pinfunction "2_2") (pintype "passive"))
      (node (ref "C13") (pin "1") (pinfunction "1_1") (pintype "passive"))
      (node (ref "C14") (pin "1") (pinfunction "1_1") (pintype "passive"))
      (node (ref "C15") (pin "1") (pinfunction "1_1") (pintype "passive"))
      (node (ref "C16") (pin "1") (pinfunction "1_1") (pintype "passive"))
      (node (ref "C17") (pin "1") (pinfunction "1_1") (pintype "passive"))
      (node (ref "C18") (pin "1") (pinfunction "1_1") (pintype "passive"))
      (node (ref "C19") (pin "1") (pinfunction "1_1") (pintype "passive"))
      (node (ref "C2") (pin "1") (pinfunction "1_1") (pintype "passive"))
      (node (ref "C20") (pin "1") (pinfunction "1_1") (pintype "passive"))
      (node (ref "C21") (pin "1") (pinfunction "1_1") (pintype "passive"))
      (node (ref "C22") (pin "1") (pinfunction "1_1") (pintype "passive"))
      (node (ref "C23") (pin "1") (pinfunction "1_1") (pintype "passive"))
      (node (ref "C24") (pin "1") (pinfunction "1_1") (pintype "passive"))
      (node (ref "C5") (pin "-") (pinfunction "-_-") (pintype "passive"))
      (node (ref "C6") (pin "-") (pinfunction "-_-") (pintype "passive"))
      (node (ref "C8") (pin "2") (pinfunction "2_2") (pintype "passive"))
      (node (ref "IC1") (pin "5") (pinfunction "2IN+_5") (pintype "input"))
      (node (ref "IC2") (pin "2") (pinfunction "-INPUT_2") (pintype "bidirectional"))
      (node (ref "IC2") (pin "4") (pinfunction "GND_4") (pintype "bidirectional"))
      (node (ref "J1") (pin "10") (pinfunction "SHIELD_10") (pintype "power_in"))
      (node (ref "J1") (pin "11") (pinfunction "SHIELD_11") (pintype "power_in"))
      (node (ref "J1") (pin "5") (pinfunction "GND_5") (pintype "power_in"))
      (node (ref "J1") (pin "6") (pinfunction "SHIELD_6") (pintype "power_in"))
      (node (ref "J1") (pin "7") (pinfunction "SHIELD_7") (pintype "power_in"))
      (node (ref "J1") (pin "8") (pinfunction "SHIELD_8") (pintype "power_in"))
      (node (ref "J1") (pin "9") (pinfunction "SHIELD_9") (pintype "power_in"))
      (node (ref "J2") (pin "4") (pinfunction "4_4") (pintype "passive"))
      (node (ref "J3") (pin "1") (pinfunction "1_1") (pintype "passive"))
      (node (ref "J4") (pin "2") (pinfunction "2_2") (pintype "passive"))
      (node (ref "J5") (pin "3") (pinfunction "3_3") (pintype "passive"))
      (node (ref "J6") (pin "1") (pinfunction "1_1") (pintype "passive"))
      (node (ref "J7") (pin "1") (pinfunction "1_1") (pintype "passive"))
      (node (ref "J8") (pin "6") (pinfunction "6_6") (pintype "bidirectional"))
      (node (ref "J9") (pin "7") (pinfunction "7_7") (pintype "passive"))
      (node (ref "R1") (pin "1") (pinfunction "1_1") (pintype "passive"))
      (node (ref "R17") (pin "1") (pinfunction "1_1") (pintype "passive"))
      (node (ref "R18") (pin "1") (pinfunction "1_1") (pintype "passive"))
      (node (ref "R19") (pin "1") (pinfunction "1_1") (pintype "passive"))
      (node (ref "R4") (pin "2") (pinfunction "2_2") (pintype "passive"))
      (node (ref "R9") (pin "1") (pinfunction "1_1") (pintype "passive"))
      (node (ref "TS53YL104MR1") (pin "3") (pinfunction "C_3") (pintype "bidirectional"))
      (node (ref "TS53YL104MR10") (pin "3") (pinfunction "C_3") (pintype "bidirectional"))
      (node (ref "U1") (pin "3") (pinfunction "GND_3") (pintype "power_in"))
      (node (ref "U1") (pin "8") (pinfunction "AGND_8") (pintype "power_in"))
    )
    (net (code "33") (name "GYRO_I2C_SCL") (class "Default")
      (node (ref "A1") (pin "CN11_51") (pinfunction "PF1_CN11_51") (pintype "bidirectional"))
      (node (ref "J5") (pin "2") (pinfunction "2_2") (pintype "passive"))
    )
    (net (code "34") (name "GYRO_I2C_SDA") (class "Default")
      (node (ref "A1") (pin "CN11_53") (pinfunction "PF0_CN11_53") (pintype "bidirectional"))
      (node (ref "J5") (pin "1") (pinfunction "1_1") (pintype "passive"))
    )
    (net (code "35") (name "JOYSTICK_SW") (class "Default")
      (node (ref "A1") (pin "CN11_59") (pinfunction "PG0_CN11_59") (pintype "bidirectional"))
      (node (ref "J9") (pin "10") (pinfunction "10_10") (pintype "passive"))
    )
    (net (code "36") (name "Net-(C3-Pad2)") (class "Default")
      (node (ref "C3") (pin "2") (pinfunction "2_2") (pintype "passive"))
      (node (ref "R1") (pin "2") (pinfunction "2_2") (pintype "passive"))
      (node (ref "R5") (pin "1") (pinfunction "1_1") (pintype "passive"))
    )
    (net (code "37") (name "Net-(C4-Pad1)") (class "Default")
      (node (ref "C4") (pin "1") (pinfunction "1_1") (pintype "passive"))
      (node (ref "R8") (pin "2") (pinfunction "2_2") (pintype "passive"))
    )
    (net (code "38") (name "Net-(C9-Pad1)") (class "Default")
      (node (ref "C9") (pin "1") (pinfunction "1_1") (pintype "passive"))
      (node (ref "R11") (pin "2") (pinfunction "2_2") (pintype "passive"))
    )
    (net (code "39") (name "Net-(IC2-+INPUT)") (class "Default")
      (node (ref "IC2") (pin "3") (pinfunction "+INPUT_3") (pintype "bidirectional"))
      (node (ref "TS53YL104MR1") (pin "2") (pinfunction "B_2") (pintype "bidirectional"))
    )
    (net (code "40") (name "Net-(IC2-BYPASS)") (class "Default")
      (node (ref "C5") (pin "+") (pinfunction "+_+") (pintype "passive"))
      (node (ref "IC2") (pin "7") (pinfunction "BYPASS_7") (pintype "bidirectional"))
    )
    (net (code "41") (name "Net-(IC2-GAIN_1)") (class "Default")
      (node (ref "IC2") (pin "1") (pinfunction "GAIN_1_1") (pintype "bidirectional"))
      (node (ref "R11") (pin "1") (pinfunction "1_1") (pintype "passive"))
    )
    (net (code "42") (name "Net-(IC2-GAIN_2)") (class "Default")
      (node (ref "C9") (pin "2") (pinfunction "2_2") (pintype "passive"))
      (node (ref "IC2") (pin "8") (pinfunction "GAIN_2_8") (pintype "bidirectional"))
    )
    (net (code "43") (name "Net-(IC2-VOUT)") (class "Default")
      (node (ref "C7") (pin "+") (pinfunction "+_+") (pintype "passive"))
      (node (ref "C8") (pin "1") (pinfunction "1_1") (pintype "passive"))
      (node (ref "IC2") (pin "5") (pinfunction "VOUT_5") (pintype "bidirectional"))
    )
    (net (code "44") (name "Net-(J3-Pad3)") (class "Default")
      (node (ref "J3") (pin "3") (pinfunction "3_3") (pintype "passive"))
      (node (ref "R14") (pin "1") (pinfunction "1_1") (pintype "passive"))
    )
    (net (code "45") (name "Net-(R2-Pad2)") (class "Default")
      (node (ref "R2") (pin "2") (pinfunction "2_2") (pintype "passive"))
      (node (ref "R3") (pin "2") (pinfunction "2_2") (pintype "passive"))
      (node (ref "R4") (pin "1") (pinfunction "1_1") (pintype "passive"))
    )
    (net (code "46") (name "Net-(TS53YL104MR1-A)") (class "Default")
      (node (ref "R12") (pin "2") (pinfunction "2_2") (pintype "passive"))
      (node (ref "TS53YL104MR1") (pin "1") (pinfunction "A_1") (pintype "bidirectional"))
    )
    (net (code "47") (name "Net-(TS53YL104MR10-A)") (class "Default")
      (node (ref "R5") (pin "2") (pinfunction "2_2") (pintype "passive"))
      (node (ref "TS53YL104MR10") (pin "1") (pinfunction "A_1") (pintype "bidirectional"))
    )
    (net (code "48") (name "Net-(TS53YL104MR10-B)") (class "Default")
      (node (ref "R6") (pin "1") (pinfunction "1_1") (pintype "passive"))
      (node (ref "TS53YL104MR10") (pin "2") (pinfunction "B_2") (pintype "bidirectional"))
    )
    (net (code "49") (name "Net-(U1-CAP+)") (class "Default")
      (node (ref "C12") (pin "2") (pinfunction "2_2") (pintype "passive"))
      (node (ref "U1") (pin "2") (pinfunction "CAP+_2") (pintype "bidirectional"))
    )
    (net (code "50") (name "Net-(U1-CAP-)") (class "Default")
      (node (ref "C12") (pin "1") (pinfunction "1_1") (pintype "passive"))
      (node (ref "U1") (pin "4") (pinfunction "CAP-_4") (pintype "bidirectional"))
    )
    (net (code "51") (name "Net-(U1-FB)") (class "Default")
      (node (ref "R15") (pin "1") (pinfunction "1_1") (pintype "passive"))
      (node (ref "R16") (pin "2") (pinfunction "2_2") (pintype "passive"))
      (node (ref "U1") (pin "7") (pinfunction "FB_7") (pintype "input"))
    )
    (net (code "52") (name "POWERAMP_AUDIO_OUT") (class "Default")
      (node (ref "C7") (pin "-") (pinfunction "-_-") (pintype "passive"))
      (node (ref "J7") (pin "2") (pinfunction "2_2") (pintype "passive"))
    )
    (net (code "53") (name "PREAMP_AUDIO_OUT") (class "Default")
      (node (ref "C4") (pin "2") (pinfunction "2_2") (pintype "passive"))
      (node (ref "J6") (pin "2") (pinfunction "2_2") (pintype "passive"))
      (node (ref "J6") (pin "3") (pinfunction "3_3") (pintype "passive"))
      (node (ref "R9") (pin "2") (pinfunction "2_2") (pintype "passive"))
    )
    (net (code "54") (name "SD_CLK") (class "Default")
      (node (ref "A1") (pin "CN11_1") (pinfunction "PC10_CN11_1") (pintype "bidirectional"))
      (node (ref "J8") (pin "4") (pinfunction "4_4") (pintype "bidirectional"))
    )
    (net (code "55") (name "SD_CS") (class "Default")
      (node (ref "A1") (pin "CN12_42") (pinfunction "PF10_CN12_42") (pintype "bidirectional"))
      (node (ref "J8") (pin "2") (pinfunction "2_2") (pintype "bidirectional"))
    )
    (net (code "56") (name "SD_DI") (class "Default")
      (node (ref "A1") (pin "CN12_22") (pinfunction "PB2_CN12_22") (pintype "bidirectional"))
      (node (ref "J8") (pin "3") (pinfunction "3_3") (pintype "bidirectional"))
    )
    (net (code "57") (name "SD_DO") (class "Default")
      (node (ref "A1") (pin "CN11_2") (pinfunction "PC11_CN11_2") (pintype "bidirectional"))
      (node (ref "J8") (pin "5") (pinfunction "5_5") (pintype "bidirectional"))
    )
    (net (code "58") (name "U5V") (class "Default")
      (node (ref "A1") (pin "CN12_8") (pinfunction "U5V_CN12_8") (pintype "power_in"))
    )
    (net (code "59") (name "USART2_RX") (class "Default")
      (node (ref "A1") (pin "CN12_37") (pinfunction "PA3_CN12_37") (pintype "bidirectional"))
    )
    (net (code "60") (name "USART2_TX") (class "Default")
      (node (ref "A1") (pin "CN12_35") (pinfunction "PA2_CN12_35") (pintype "bidirectional"))
    )
    (net (code "61") (name "USART3_RX") (class "Default")
      (node (ref "A1") (pin "CN11_69") (pinfunction "PD9_CN11_69") (pintype "bidirectional"))
    )
    (net (code "62") (name "USART3_TX") (class "Default")
      (node (ref "A1") (pin "CN12_10") (pinfunction "PD8_CN12_10") (pintype "bidirectional"))
    )
    (net (code "63") (name "VBAT_CN11") (class "Default")
      (node (ref "A1") (pin "CN11_33") (pinfunction "VBAT_CN11_CN11_33") (pintype "power_in"))
    )
    (net (code "64") (name "VDD_CN11") (class "Default")
      (node (ref "A1") (pin "CN11_5") (pinfunction "VDD_CN11_CN11_5") (pintype "power_in"))
    )
    (net (code "65") (name "VIN_CN8") (class "Default")
      (node (ref "A1") (pin "CN8_15") (pinfunction "VIN_CN8_CN8_15") (pintype "power_in"))
    )
    (net (code "66") (name "VIN_CN11") (class "Default")
      (node (ref "A1") (pin "CN11_24") (pinfunction "VIN_CN11_CN11_24") (pintype "power_in"))
    )
    (net (code "67") (name "unconnected-(A1A-BOOT0-PadCN11_7)") (class "Default")
      (node (ref "A1") (pin "CN11_7") (pinfunction "BOOT0_CN11_7") (pintype "bidirectional"))
    )
    (net (code "68") (name "unconnected-(A1A-IOREF_CN11-PadCN11_12)") (class "Default")
      (node (ref "A1") (pin "CN11_12") (pinfunction "IOREF_CN11_CN11_12") (pintype "bidirectional"))
    )
    (net (code "69") (name "unconnected-(A1A-PA1-PadCN11_30)") (class "Default")
      (node (ref "A1") (pin "CN11_30") (pinfunction "PA1_CN11_30") (pintype "bidirectional"))
    )
    (net (code "70") (name "unconnected-(A1A-PA13-PadCN11_13)") (class "Default")
      (node (ref "A1") (pin "CN11_13") (pinfunction "PA13_CN11_13") (pintype "bidirectional"))
    )
    (net (code "71") (name "unconnected-(A1A-PA14-PadCN11_15)") (class "Default")
      (node (ref "A1") (pin "CN11_15") (pinfunction "PA14_CN11_15") (pintype "bidirectional"))
    )
    (net (code "72") (name "unconnected-(A1A-PA15-PadCN11_17)") (class "Default")
      (node (ref "A1") (pin "CN11_17") (pinfunction "PA15_CN11_17") (pintype "bidirectional"))
    )
    (net (code "73") (name "unconnected-(A1A-PB7-PadCN11_21)") (class "Default")
      (node (ref "A1") (pin "CN11_21") (pinfunction "PB7_CN11_21") (pintype "bidirectional"))
    )
    (net (code "74") (name "unconnected-(A1A-PC1-PadCN11_36)") (class "Default")
      (node (ref "A1") (pin "CN11_36") (pinfunction "PC1_CN11_36") (pintype "bidirectional"))
    )
    (net (code "75") (name "unconnected-(A1A-PC3-PadCN11_37)") (class "Default")
      (node (ref "A1") (pin "CN11_37") (pinfunction "PC3_CN11_37") (pintype "bidirectional"))
    )
    (net (code "76") (name "unconnected-(A1A-PC12-PadCN11_3)") (class "Default")
      (node (ref "A1") (pin "CN11_3") (pinfunction "PC12_CN11_3") (pintype "bidirectional"))
    )
    (net (code "77") (name "unconnected-(A1A-PC13-PadCN11_23)") (class "Default")
      (node (ref "A1") (pin "CN11_23") (pinfunction "PC13_CN11_23") (pintype "bidirectional"))
    )
    (net (code "78") (name "unconnected-(A1A-PC14-PadCN11_25)") (class "Default")
      (node (ref "A1") (pin "CN11_25") (pinfunction "PC14_CN11_25") (pintype "bidirectional"))
    )
    (net (code "79") (name "unconnected-(A1A-PC15-PadCN11_27)") (class "Default")
      (node (ref "A1") (pin "CN11_27") (pinfunction "PC15_CN11_27") (pintype "bidirectional"))
    )
    (net (code "80") (name "unconnected-(A1A-PD0-PadCN11_57)") (class "Default")
      (node (ref "A1") (pin "CN11_57") (pinfunction "PD0_CN11_57") (pintype "bidirectional"))
    )
    (net (code "81") (name "unconnected-(A1A-PD1-PadCN11_55)") (class "Default")
      (node (ref "A1") (pin "CN11_55") (pinfunction "PD1_CN11_55") (pintype "bidirectional"))
    )
    (net (code "82") (name "unconnected-(A1A-PD2-PadCN11_4)") (class "Default")
      (node (ref "A1") (pin "CN11_4") (pinfunction "PD2_CN11_4") (pintype "bidirectional"))
    )
    (net (code "83") (name "unconnected-(A1A-PD3-PadCN11_40)") (class "Default")
      (node (ref "A1") (pin "CN11_40") (pinfunction "PD3_CN11_40") (pintype "bidirectional"))
    )
    (net (code "84") (name "unconnected-(A1A-PD4-PadCN11_39)") (class "Default")
      (node (ref "A1") (pin "CN11_39") (pinfunction "PD4_CN11_39") (pintype "bidirectional"))
    )
    (net (code "85") (name "unconnected-(A1A-PD5-PadCN11_41)") (class "Default")
      (node (ref "A1") (pin "CN11_41") (pinfunction "PD5_CN11_41") (pintype "bidirectional"))
    )
    (net (code "86") (name "unconnected-(A1A-PD6-PadCN11_43)") (class "Default")
      (node (ref "A1") (pin "CN11_43") (pinfunction "PD6_CN11_43") (pintype "bidirectional"))
    )
    (net (code "87") (name "unconnected-(A1A-PD7-PadCN11_45)") (class "Default")
      (node (ref "A1") (pin "CN11_45") (pinfunction "PD7_CN11_45") (pintype "bidirectional"))
    )
    (net (code "88") (name "unconnected-(A1A-PE1-PadCN11_61)") (class "Default")
      (node (ref "A1") (pin "CN11_61") (pinfunction "PE1_CN11_61") (pintype "bidirectional"))
    )
    (net (code "89") (name "unconnected-(A1A-PE2-PadCN11_46)") (class "Default")
      (node (ref "A1") (pin "CN11_46") (pinfunction "PE2_CN11_46") (pintype "bidirectional"))
    )
    (net (code "90") (name "unconnected-(A1A-PE3-PadCN11_47)") (class "Default")
      (node (ref "A1") (pin "CN11_47") (pinfunction "PE3_CN11_47") (pintype "bidirectional"))
    )
    (net (code "91") (name "unconnected-(A1A-PE4-PadCN11_48)") (class "Default")
      (node (ref "A1") (pin "CN11_48") (pinfunction "PE4_CN11_48") (pintype "bidirectional"))
    )
    (net (code "92") (name "unconnected-(A1A-PE5-PadCN11_50)") (class "Default")
      (node (ref "A1") (pin "CN11_50") (pinfunction "PE5_CN11_50") (pintype "bidirectional"))
    )
    (net (code "93") (name "unconnected-(A1A-PE6-PadCN11_62)") (class "Default")
      (node (ref "A1") (pin "CN11_62") (pinfunction "PE6_CN11_62") (pintype "bidirectional"))
    )
    (net (code "94") (name "unconnected-(A1A-PF2-PadCN11_52)") (class "Default")
      (node (ref "A1") (pin "CN11_52") (pinfunction "PF2_CN11_52") (pintype "bidirectional"))
    )
    (net (code "95") (name "unconnected-(A1A-PF8-PadCN11_54)") (class "Default")
      (node (ref "A1") (pin "CN11_54") (pinfunction "PF8_CN11_54") (pintype "bidirectional"))
    )
    (net (code "96") (name "unconnected-(A1A-PF9-PadCN11_56)") (class "Default")
      (node (ref "A1") (pin "CN11_56") (pinfunction "PF9_CN11_56") (pintype "bidirectional"))
    )
    (net (code "97") (name "unconnected-(A1A-PG1-PadCN11_58)") (class "Default")
      (node (ref "A1") (pin "CN11_58") (pinfunction "PG1_CN11_58") (pintype "bidirectional"))
    )
    (net (code "98") (name "unconnected-(A1A-PG2-PadCN11_42)") (class "Default")
      (node (ref "A1") (pin "CN11_42") (pinfunction "PG2_CN11_42") (pintype "bidirectional"))
    )
    (net (code "99") (name "unconnected-(A1A-PG3-PadCN11_44)") (class "Default")
      (node (ref "A1") (pin "CN11_44") (pinfunction "PG3_CN11_44") (pintype "bidirectional"))
    )
    (net (code "100") (name "unconnected-(A1A-PG9-PadCN11_63)") (class "Default")
      (node (ref "A1") (pin "CN11_63") (pinfunction "PG9_CN11_63") (pintype "bidirectional"))
    )
    (net (code "101") (name "unconnected-(A1A-PG10-PadCN11_66)") (class "Default")
      (node (ref "A1") (pin "CN11_66") (pinfunction "PG10_CN11_66") (pintype "bidirectional"))
    )
    (net (code "102") (name "unconnected-(A1A-PG11-PadCN11_70)") (class "Default")
      (node (ref "A1") (pin "CN11_70") (pinfunction "PG11_CN11_70") (pintype "bidirectional"))
    )
    (net (code "103") (name "unconnected-(A1A-PG12-PadCN11_65)") (class "Default")
      (node (ref "A1") (pin "CN11_65") (pinfunction "PG12_CN11_65") (pintype "bidirectional"))
    )
    (net (code "104") (name "unconnected-(A1A-PG13-PadCN11_68)") (class "Default")
      (node (ref "A1") (pin "CN11_68") (pinfunction "PG13_CN11_68") (pintype "bidirectional"))
    )
    (net (code "105") (name "unconnected-(A1A-PG15-PadCN11_64)") (class "Default")
      (node (ref "A1") (pin "CN11_64") (pinfunction "PG15_CN11_64") (pintype "bidirectional"))
    )
    (net (code "106") (name "unconnected-(A1A-PH0-PadCN11_29)") (class "Default")
      (node (ref "A1") (pin "CN11_29") (pinfunction "PH0_CN11_29") (pintype "bidirectional"))
    )
    (net (code "107") (name "unconnected-(A1A-PH1-PadCN11_31)") (class "Default")
      (node (ref "A1") (pin "CN11_31") (pinfunction "PH1_CN11_31") (pintype "bidirectional"))
    )
    (net (code "108") (name "unconnected-(A1A-RESET_CN11-PadCN11_14)") (class "Default")
      (node (ref "A1") (pin "CN11_14") (pinfunction "RESET_CN11_CN11_14") (pintype "bidirectional"))
    )
    (net (code "109") (name "unconnected-(A1B-PA7-PadCN12_15)") (class "Default")
      (node (ref "A1") (pin "CN12_15") (pinfunction "PA7_CN12_15") (pintype "bidirectional"))
    )
    (net (code "110") (name "unconnected-(A1B-PA8-PadCN12_23)") (class "Default")
      (node (ref "A1") (pin "CN12_23") (pinfunction "PA8_CN12_23") (pintype "bidirectional"))
    )
    (net (code "111") (name "unconnected-(A1B-PA9-PadCN12_21)") (class "Default")
      (node (ref "A1") (pin "CN12_21") (pinfunction "PA9_CN12_21") (pintype "bidirectional"))
    )
    (net (code "112") (name "unconnected-(A1B-PA10-PadCN12_33)") (class "Default")
      (node (ref "A1") (pin "CN12_33") (pinfunction "PA10_CN12_33") (pintype "bidirectional"))
    )
    (net (code "113") (name "unconnected-(A1B-PA11-PadCN12_14)") (class "Default")
      (node (ref "A1") (pin "CN12_14") (pinfunction "PA11_CN12_14") (pintype "bidirectional"))
    )
    (net (code "114") (name "unconnected-(A1B-PA12-PadCN12_12)") (class "Default")
      (node (ref "A1") (pin "CN12_12") (pinfunction "PA12_CN12_12") (pintype "bidirectional"))
    )
    (net (code "115") (name "unconnected-(A1B-PB4-PadCN12_27)") (class "Default")
      (node (ref "A1") (pin "CN12_27") (pinfunction "PB4_CN12_27") (pintype "bidirectional"))
    )
    (net (code "116") (name "unconnected-(A1B-PB6-PadCN12_17)") (class "Default")
      (node (ref "A1") (pin "CN12_17") (pinfunction "PB6_CN12_17") (pintype "bidirectional"))
    )
    (net (code "117") (name "unconnected-(A1B-PB8-PadCN12_3)") (class "Default")
      (node (ref "A1") (pin "CN12_3") (pinfunction "PB8_CN12_3") (pintype "bidirectional"))
    )
    (net (code "118") (name "unconnected-(A1B-PB9-PadCN12_5)") (class "Default")
      (node (ref "A1") (pin "CN12_5") (pinfunction "PB9_CN12_5") (pintype "bidirectional"))
    )
    (net (code "119") (name "unconnected-(A1B-PB10-PadCN12_25)") (class "Default")
      (node (ref "A1") (pin "CN12_25") (pinfunction "PB10_CN12_25") (pintype "bidirectional"))
    )
    (net (code "120") (name "unconnected-(A1B-PB11-PadCN12_18)") (class "Default")
      (node (ref "A1") (pin "CN12_18") (pinfunction "PB11_CN12_18") (pintype "bidirectional"))
    )
    (net (code "121") (name "unconnected-(A1B-PB12-PadCN12_16)") (class "Default")
      (node (ref "A1") (pin "CN12_16") (pinfunction "PB12_CN12_16") (pintype "bidirectional"))
    )
    (net (code "122") (name "unconnected-(A1B-PB13-PadCN12_30)") (class "Default")
      (node (ref "A1") (pin "CN12_30") (pinfunction "PB13_CN12_30") (pintype "bidirectional"))
    )
    (net (code "123") (name "unconnected-(A1B-PB14-PadCN12_28)") (class "Default")
      (node (ref "A1") (pin "CN12_28") (pinfunction "PB14_CN12_28") (pintype "bidirectional"))
    )
    (net (code "124") (name "unconnected-(A1B-PB15-PadCN12_26)") (class "Default")
      (node (ref "A1") (pin "CN12_26") (pinfunction "PB15_CN12_26") (pintype "bidirectional"))
    )
    (net (code "125") (name "unconnected-(A1B-PC4-PadCN12_34)") (class "Default")
      (node (ref "A1") (pin "CN12_34") (pinfunction "PC4_CN12_34") (pintype "bidirectional"))
    )
    (net (code "126") (name "unconnected-(A1B-PC5-PadCN12_6)") (class "Default")
      (node (ref "A1") (pin "CN12_6") (pinfunction "PC5_CN12_6") (pintype "bidirectional"))
    )
    (net (code "127") (name "unconnected-(A1B-PC6-PadCN12_4)") (class "Default")
      (node (ref "A1") (pin "CN12_4") (pinfunction "PC6_CN12_4") (pintype "bidirectional"))
    )
    (net (code "128") (name "unconnected-(A1B-PC7-PadCN12_19)") (class "Default")
      (node (ref "A1") (pin "CN12_19") (pinfunction "PC7_CN12_19") (pintype "bidirectional"))
    )
    (net (code "129") (name "unconnected-(A1B-PD10-PadCN12_65)") (class "Default")
      (node (ref "A1") (pin "CN12_65") (pinfunction "PD10_CN12_65") (pintype "bidirectional"))
    )
    (net (code "130") (name "unconnected-(A1B-PD11-PadCN12_45)") (class "Default")
      (node (ref "A1") (pin "CN12_45") (pinfunction "PD11_CN12_45") (pintype "bidirectional"))
    )
    (net (code "131") (name "unconnected-(A1B-PD12-PadCN12_43)") (class "Default")
      (node (ref "A1") (pin "CN12_43") (pinfunction "PD12_CN12_43") (pintype "bidirectional"))
    )
    (net (code "132") (name "unconnected-(A1B-PD13-PadCN12_41)") (class "Default")
      (node (ref "A1") (pin "CN12_41") (pinfunction "PD13_CN12_41") (pintype "bidirectional"))
    )
    (net (code "133") (name "unconnected-(A1B-PD14-PadCN12_46)") (class "Default")
      (node (ref "A1") (pin "CN12_46") (pinfunction "PD14_CN12_46") (pintype "bidirectional"))
    )
    (net (code "134") (name "unconnected-(A1B-PD15-PadCN12_48)") (class "Default")
      (node (ref "A1") (pin "CN12_48") (pinfunction "PD15_CN12_48") (pintype "bidirectional"))
    )
    (net (code "135") (name "unconnected-(A1B-PE0-PadCN12_64)") (class "Default")
      (node (ref "A1") (pin "CN12_64") (pinfunction "PE0_CN12_64") (pintype "bidirectional"))
    )
    (net (code "136") (name "unconnected-(A1B-PE7-PadCN12_44)") (class "Default")
      (node (ref "A1") (pin "CN12_44") (pinfunction "PE7_CN12_44") (pintype "bidirectional"))
    )
    (net (code "137") (name "unconnected-(A1B-PE9-PadCN12_52)") (class "Default")
      (node (ref "A1") (pin "CN12_52") (pinfunction "PE9_CN12_52") (pintype "bidirectional"))
    )
    (net (code "138") (name "unconnected-(A1B-PE10-PadCN12_47)") (class "Default")
      (node (ref "A1") (pin "CN12_47") (pinfunction "PE10_CN12_47") (pintype "bidirectional"))
    )
    (net (code "139") (name "unconnected-(A1B-PE11-PadCN12_56)") (class "Default")
      (node (ref "A1") (pin "CN12_56") (pinfunction "PE11_CN12_56") (pintype "bidirectional"))
    )
    (net (code "140") (name "unconnected-(A1B-PE12-PadCN12_49)") (class "Default")
      (node (ref "A1") (pin "CN12_49") (pinfunction "PE12_CN12_49") (pintype "bidirectional"))
    )
    (net (code "141") (name "unconnected-(A1B-PE13-PadCN12_55)") (class "Default")
      (node (ref "A1") (pin "CN12_55") (pinfunction "PE13_CN12_55") (pintype "bidirectional"))
    )
    (net (code "142") (name "unconnected-(A1B-PE14-PadCN12_51)") (class "Default")
      (node (ref "A1") (pin "CN12_51") (pinfunction "PE14_CN12_51") (pintype "bidirectional"))
    )
    (net (code "143") (name "unconnected-(A1B-PE15-PadCN12_53)") (class "Default")
      (node (ref "A1") (pin "CN12_53") (pinfunction "PE15_CN12_53") (pintype "bidirectional"))
    )
    (net (code "144") (name "unconnected-(A1B-PF3-PadCN12_58)") (class "Default")
      (node (ref "A1") (pin "CN12_58") (pinfunction "PF3_CN12_58") (pintype "bidirectional"))
    )
    (net (code "145") (name "unconnected-(A1B-PF4-PadCN12_38)") (class "Default")
      (node (ref "A1") (pin "CN12_38") (pinfunction "PF4_CN12_38") (pintype "bidirectional"))
    )
    (net (code "146") (name "unconnected-(A1B-PF5-PadCN12_36)") (class "Default")
      (node (ref "A1") (pin "CN12_36") (pinfunction "PF5_CN12_36") (pintype "bidirectional"))
    )
    (net (code "147") (name "unconnected-(A1B-PF11-PadCN12_62)") (class "Default")
      (node (ref "A1") (pin "CN12_62") (pinfunction "PF11_CN12_62") (pintype "bidirectional"))
    )
    (net (code "148") (name "unconnected-(A1B-PF13-PadCN12_57)") (class "Default")
      (node (ref "A1") (pin "CN12_57") (pinfunction "PF13_CN12_57") (pintype "bidirectional"))
    )
    (net (code "149") (name "unconnected-(A1B-PF14-PadCN12_50)") (class "Default")
      (node (ref "A1") (pin "CN12_50") (pinfunction "PF14_CN12_50") (pintype "bidirectional"))
    )
    (net (code "150") (name "unconnected-(A1B-PF15-PadCN12_60)") (class "Default")
      (node (ref "A1") (pin "CN12_60") (pinfunction "PF15_CN12_60") (pintype "bidirectional"))
    )
    (net (code "151") (name "unconnected-(A1B-PG4-PadCN12_69)") (class "Default")
      (node (ref "A1") (pin "CN12_69") (pinfunction "PG4_CN12_69") (pintype "bidirectional"))
    )
    (net (code "152") (name "unconnected-(A1B-PG5-PadCN12_68)") (class "Default")
      (node (ref "A1") (pin "CN12_68") (pinfunction "PG5_CN12_68") (pintype "bidirectional"))
    )
    (net (code "153") (name "unconnected-(A1B-PG6-PadCN12_70)") (class "Default")
      (node (ref "A1") (pin "CN12_70") (pinfunction "PG6_CN12_70") (pintype "bidirectional"))
    )
    (net (code "154") (name "unconnected-(A1B-PG7-PadCN12_67)") (class "Default")
      (node (ref "A1") (pin "CN12_67") (pinfunction "PG7_CN12_67") (pintype "bidirectional"))
    )
    (net (code "155") (name "unconnected-(A1B-PG8-PadCN12_66)") (class "Default")
      (node (ref "A1") (pin "CN12_66") (pinfunction "PG8_CN12_66") (pintype "bidirectional"))
    )
    (net (code "156") (name "unconnected-(A1B-PG14-PadCN12_61)") (class "Default")
      (node (ref "A1") (pin "CN12_61") (pinfunction "PG14_CN12_61") (pintype "bidirectional"))
    )
    (net (code "157") (name "unconnected-(A1C-D43{slash}SDMMC_D0-PadCN8_2)") (class "Default")
      (node (ref "A1") (pin "CN8_2") (pinfunction "D43/SDMMC_D0_CN8_2") (pintype "bidirectional"))
    )
    (net (code "158") (name "unconnected-(A1C-D44{slash}SDMMC_D1{slash}I2S_A_CKIN-PadCN8_4)") (class "Default")
      (node (ref "A1") (pin "CN8_4") (pinfunction "D44/SDMMC_D1/I2S_A_CKIN_CN8_4") (pintype "bidirectional"))
    )
    (net (code "159") (name "unconnected-(A1C-D45{slash}SDMMC_D2-PadCN8_6)") (class "Default")
      (node (ref "A1") (pin "CN8_6") (pinfunction "D45/SDMMC_D2_CN8_6") (pintype "bidirectional"))
    )
    (net (code "160") (name "unconnected-(A1C-D46{slash}SDMMC_D3-PadCN8_8)") (class "Default")
      (node (ref "A1") (pin "CN8_8") (pinfunction "D46/SDMMC_D3_CN8_8") (pintype "bidirectional"))
    )
    (net (code "161") (name "unconnected-(A1C-D47{slash}SDMMC_CK-PadCN8_10)") (class "Default")
      (node (ref "A1") (pin "CN8_10") (pinfunction "D47/SDMMC_CK_CN8_10") (pintype "bidirectional"))
    )
    (net (code "162") (name "unconnected-(A1C-D48{slash}SDMMC_CMD-PadCN8_12)") (class "Default")
      (node (ref "A1") (pin "CN8_12") (pinfunction "D48/SDMMC_CMD_CN8_12") (pintype "bidirectional"))
    )
    (net (code "163") (name "unconnected-(A1C-D49{slash}IO-PadCN8_14)") (class "Default")
      (node (ref "A1") (pin "CN8_14") (pinfunction "D49/IO_CN8_14") (pintype "bidirectional"))
    )
    (net (code "164") (name "unconnected-(A1C-D50{slash}IO-PadCN8_16)") (class "Default")
      (node (ref "A1") (pin "CN8_16") (pinfunction "D50/IO_CN8_16") (pintype "bidirectional"))
    )
    (net (code "165") (name "unconnected-(A1C-IOREF_CN8-PadCN8_3)") (class "Default")
      (node (ref "A1") (pin "CN8_3") (pinfunction "IOREF_CN8_CN8_3") (pintype "bidirectional"))
    )
    (net (code "166") (name "unconnected-(A1C-RESET_CN8-PadCN8_5)") (class "Default")
      (node (ref "A1") (pin "CN8_5") (pinfunction "RESET_CN8_CN8_5") (pintype "bidirectional"))
    )
    (net (code "167") (name "unconnected-(A1D-A0{slash}ADC123_IN3-PadCN9_1)") (class "Default")
      (node (ref "A1") (pin "CN9_1") (pinfunction "A0/ADC123_IN3_CN9_1") (pintype "input"))
    )
    (net (code "168") (name "unconnected-(A1D-A1{slash}ADC123_IN10-PadCN9_3)") (class "Default")
      (node (ref "A1") (pin "CN9_3") (pinfunction "A1/ADC123_IN10_CN9_3") (pintype "input"))
    )
    (net (code "169") (name "unconnected-(A1D-A2{slash}ADC123_IN13-PadCN9_5)") (class "Default")
      (node (ref "A1") (pin "CN9_5") (pinfunction "A2/ADC123_IN13_CN9_5") (pintype "input"))
    )
    (net (code "170") (name "unconnected-(A1D-A3{slash}ADC3_IN9-PadCN9_7)") (class "Default")
      (node (ref "A1") (pin "CN9_7") (pinfunction "A3/ADC3_IN9_CN9_7") (pintype "input"))
    )
    (net (code "171") (name "unconnected-(A1D-A4{slash}ADC3_IN15{slash}I2C1_SDA-PadCN9_9)") (class "Default")
      (node (ref "A1") (pin "CN9_9") (pinfunction "A4/ADC3_IN15/I2C1_SDA_CN9_9") (pintype "input"))
    )
    (net (code "172") (name "unconnected-(A1D-A5{slash}ADC3_IN8{slash}I2C1_SCL-PadCN9_11)") (class "Default")
      (node (ref "A1") (pin "CN9_11") (pinfunction "A5/ADC3_IN8/I2C1_SCL_CN9_11") (pintype "input"))
    )
    (net (code "173") (name "unconnected-(A1D-D51{slash}USART_B_SCLK-PadCN9_2)") (class "Default")
      (node (ref "A1") (pin "CN9_2") (pinfunction "D51/USART_B_SCLK_CN9_2") (pintype "bidirectional"))
    )
    (net (code "174") (name "unconnected-(A1D-D52{slash}USART_B_RX-PadCN9_4)") (class "Default")
      (node (ref "A1") (pin "CN9_4") (pinfunction "D52/USART_B_RX_CN9_4") (pintype "bidirectional"))
    )
    (net (code "175") (name "unconnected-(A1D-D53{slash}USART_B_TX-PadCN9_6)") (class "Default")
      (node (ref "A1") (pin "CN9_6") (pinfunction "D53/USART_B_TX_CN9_6") (pintype "bidirectional"))
    )
    (net (code "176") (name "unconnected-(A1D-D54{slash}USART_B_RTS-PadCN9_8)") (class "Default")
      (node (ref "A1") (pin "CN9_8") (pinfunction "D54/USART_B_RTS_CN9_8") (pintype "bidirectional"))
    )
    (net (code "177") (name "unconnected-(A1D-D55{slash}USART_B_CTS-PadCN9_10)") (class "Default")
      (node (ref "A1") (pin "CN9_10") (pinfunction "D55/USART_B_CTS_CN9_10") (pintype "bidirectional"))
    )
    (net (code "178") (name "unconnected-(A1D-D56{slash}SAI_A_MCLK-PadCN9_14)") (class "Default")
      (node (ref "A1") (pin "CN9_14") (pinfunction "D56/SAI_A_MCLK_CN9_14") (pintype "bidirectional"))
    )
    (net (code "179") (name "unconnected-(A1D-D57{slash}SAI_A_FS-PadCN9_16)") (class "Default")
      (node (ref "A1") (pin "CN9_16") (pinfunction "D57/SAI_A_FS_CN9_16") (pintype "bidirectional"))
    )
    (net (code "180") (name "unconnected-(A1D-D58{slash}SAI_A_SCK-PadCN9_18)") (class "Default")
      (node (ref "A1") (pin "CN9_18") (pinfunction "D58/SAI_A_SCK_CN9_18") (pintype "bidirectional"))
    )
    (net (code "181") (name "unconnected-(A1D-D59{slash}SAI_A_SD-PadCN9_20)") (class "Default")
      (node (ref "A1") (pin "CN9_20") (pinfunction "D59/SAI_A_SD_CN9_20") (pintype "bidirectional"))
    )
    (net (code "182") (name "unconnected-(A1D-D60{slash}SAI_B_SD-PadCN9_22)") (class "Default")
      (node (ref "A1") (pin "CN9_22") (pinfunction "D60/SAI_B_SD_CN9_22") (pintype "bidirectional"))
    )
    (net (code "183") (name "unconnected-(A1D-D61{slash}SAI_B_SCK-PadCN9_24)") (class "Default")
      (node (ref "A1") (pin "CN9_24") (pinfunction "D61/SAI_B_SCK_CN9_24") (pintype "bidirectional"))
    )
    (net (code "184") (name "unconnected-(A1D-D62{slash}SAI_B_MCLK-PadCN9_26)") (class "Default")
      (node (ref "A1") (pin "CN9_26") (pinfunction "D62/SAI_B_MCLK_CN9_26") (pintype "bidirectional"))
    )
    (net (code "185") (name "unconnected-(A1D-D63{slash}SAI_B_FS-PadCN9_28)") (class "Default")
      (node (ref "A1") (pin "CN9_28") (pinfunction "D63/SAI_B_FS_CN9_28") (pintype "bidirectional"))
    )
    (net (code "186") (name "unconnected-(A1D-D64{slash}IO-PadCN9_30)") (class "Default")
      (node (ref "A1") (pin "CN9_30") (pinfunction "D64/IO_CN9_30") (pintype "bidirectional"))
    )
    (net (code "187") (name "unconnected-(A1D-D65{slash}IO-PadCN9_29)") (class "Default")
      (node (ref "A1") (pin "CN9_29") (pinfunction "D65/IO_CN9_29") (pintype "bidirectional"))
    )
    (net (code "188") (name "unconnected-(A1D-D66{slash}CAN_TX-PadCN9_27)") (class "Default")
      (node (ref "A1") (pin "CN9_27") (pinfunction "D66/CAN_TX_CN9_27") (pintype "output"))
    )
    (net (code "189") (name "unconnected-(A1D-D67{slash}CAN_RX-PadCN9_25)") (class "Default")
      (node (ref "A1") (pin "CN9_25") (pinfunction "D67/CAN_RX_CN9_25") (pintype "input"))
    )
    (net (code "190") (name "unconnected-(A1D-D68{slash}I2C_B_SDA-PadCN9_21)") (class "Default")
      (node (ref "A1") (pin "CN9_21") (pinfunction "D68/I2C_B_SDA_CN9_21") (pintype "bidirectional"))
    )
    (net (code "191") (name "unconnected-(A1D-D69{slash}I2C_B_SCL-PadCN9_19)") (class "Default")
      (node (ref "A1") (pin "CN9_19") (pinfunction "D69/I2C_B_SCL_CN9_19") (pintype "bidirectional"))
    )
    (net (code "192") (name "unconnected-(A1D-D70{slash}I2C_B_SMBA-PadCN9_17)") (class "Default")
      (node (ref "A1") (pin "CN9_17") (pinfunction "D70/I2C_B_SMBA_CN9_17") (pintype "bidirectional"))
    )
    (net (code "193") (name "unconnected-(A1D-D71{slash}IO-PadCN9_15)") (class "Default")
      (node (ref "A1") (pin "CN9_15") (pinfunction "D71/IO_CN9_15") (pintype "bidirectional"))
    )
    (net (code "194") (name "unconnected-(A1D-D72{slash}NC-PadCN9_13)") (class "Default")
      (node (ref "A1") (pin "CN9_13") (pinfunction "D72/NC_CN9_13") (pintype "bidirectional"))
    )
    (net (code "195") (name "unconnected-(A1E-D8{slash}IO-PadCN7_20)") (class "Default")
      (node (ref "A1") (pin "CN7_20") (pinfunction "D8/IO_CN7_20") (pintype "bidirectional"))
    )
    (net (code "196") (name "unconnected-(A1E-D9{slash}TIMER_B_PWM2-PadCN7_18)") (class "Default")
      (node (ref "A1") (pin "CN7_18") (pinfunction "D9/TIMER_B_PWM2_CN7_18") (pintype "bidirectional"))
    )
    (net (code "197") (name "unconnected-(A1E-D10{slash}SPI_A_CS{slash}TIM_B_PWM3-PadCN7_16)") (class "Default")
      (node (ref "A1") (pin "CN7_16") (pinfunction "D10/SPI_A_CS/TIM_B_PWM3_CN7_16") (pintype "bidirectional"))
    )
    (net (code "198") (name "unconnected-(A1E-D11{slash}SPI_A_MOSI{slash}TIM_E_PWM1-PadCN7_14)") (class "Default")
      (node (ref "A1") (pin "CN7_14") (pinfunction "D11/SPI_A_MOSI/TIM_E_PWM1_CN7_14") (pintype "bidirectional"))
    )
    (net (code "199") (name "unconnected-(A1E-D12{slash}SPI_A_MISO-PadCN7_12)") (class "Default")
      (node (ref "A1") (pin "CN7_12") (pinfunction "D12/SPI_A_MISO_CN7_12") (pintype "bidirectional"))
    )
    (net (code "200") (name "unconnected-(A1E-D13{slash}SPI_A_SCK-PadCN7_10)") (class "Default")
      (node (ref "A1") (pin "CN7_10") (pinfunction "D13/SPI_A_SCK_CN7_10") (pintype "bidirectional"))
    )
    (net (code "201") (name "unconnected-(A1E-D14{slash}I2C_A_SDA-PadCN7_4)") (class "Default")
      (node (ref "A1") (pin "CN7_4") (pinfunction "D14/I2C_A_SDA_CN7_4") (pintype "bidirectional"))
    )
    (net (code "202") (name "unconnected-(A1E-D15{slash}I2C_A_SCL-PadCN7_2)") (class "Default")
      (node (ref "A1") (pin "CN7_2") (pinfunction "D15/I2C_A_SCL_CN7_2") (pintype "bidirectional"))
    )
    (net (code "203") (name "unconnected-(A1E-D16{slash}I2S_A_MCK-PadCN7_1)") (class "Default")
      (node (ref "A1") (pin "CN7_1") (pinfunction "D16/I2S_A_MCK_CN7_1") (pintype "bidirectional"))
    )
    (net (code "204") (name "unconnected-(A1E-D17{slash}I2S_A_SD-PadCN7_3)") (class "Default")
      (node (ref "A1") (pin "CN7_3") (pinfunction "D17/I2S_A_SD_CN7_3") (pintype "bidirectional"))
    )
    (net (code "205") (name "unconnected-(A1E-D18{slash}I2S_A_CK-PadCN7_5)") (class "Default")
      (node (ref "A1") (pin "CN7_5") (pinfunction "D18/I2S_A_CK_CN7_5") (pintype "bidirectional"))
    )
    (net (code "206") (name "unconnected-(A1E-D19{slash}I2S_A_WS-PadCN7_7)") (class "Default")
      (node (ref "A1") (pin "CN7_7") (pinfunction "D19/I2S_A_WS_CN7_7") (pintype "bidirectional"))
    )
    (net (code "207") (name "unconnected-(A1E-D20{slash}I2S_B_WS-PadCN7_9)") (class "Default")
      (node (ref "A1") (pin "CN7_9") (pinfunction "D20/I2S_B_WS_CN7_9") (pintype "bidirectional"))
    )
    (net (code "208") (name "unconnected-(A1E-D21{slash}I2S_B_MCK-PadCN7_11)") (class "Default")
      (node (ref "A1") (pin "CN7_11") (pinfunction "D21/I2S_B_MCK_CN7_11") (pintype "bidirectional"))
    )
    (net (code "209") (name "unconnected-(A1E-D22{slash}I2S_B_SD{slash}SPI_B_MOSI-PadCN7_13)") (class "Default")
      (node (ref "A1") (pin "CN7_13") (pinfunction "D22/I2S_B_SD/SPI_B_MOSI_CN7_13") (pintype "bidirectional"))
    )
    (net (code "210") (name "unconnected-(A1E-D23{slash}I2S_B_CK{slash}SPI_B_SCK-PadCN7_15)") (class "Default")
      (node (ref "A1") (pin "CN7_15") (pinfunction "D23/I2S_B_CK/SPI_B_SCK_CN7_15") (pintype "bidirectional"))
    )
    (net (code "211") (name "unconnected-(A1E-D24{slash}SPI_B_NSS-PadCN7_17)") (class "Default")
      (node (ref "A1") (pin "CN7_17") (pinfunction "D24/SPI_B_NSS_CN7_17") (pintype "bidirectional"))
    )
    (net (code "212") (name "unconnected-(A1E-D25{slash}SPI_B_MISO-PadCN7_19)") (class "Default")
      (node (ref "A1") (pin "CN7_19") (pinfunction "D25/SPI_B_MISO_CN7_19") (pintype "bidirectional"))
    )
    (net (code "213") (name "unconnected-(A1F-A6{slash}ADC_A_IN-PadCN10_7)") (class "Default")
      (node (ref "A1") (pin "CN10_7") (pinfunction "A6/ADC_A_IN_CN10_7") (pintype "input"))
    )
    (net (code "214") (name "unconnected-(A1F-A7{slash}ADC_B_IN-PadCN10_9)") (class "Default")
      (node (ref "A1") (pin "CN10_9") (pinfunction "A7/ADC_B_IN_CN10_9") (pintype "input"))
    )
    (net (code "215") (name "unconnected-(A1F-A8{slash}ADC_C_IN-PadCN10_11)") (class "Default")
      (node (ref "A1") (pin "CN10_11") (pinfunction "A8/ADC_C_IN_CN10_11") (pintype "input"))
    )
    (net (code "216") (name "unconnected-(A1F-D0{slash}USART_A_RX-PadCN10_16)") (class "Default")
      (node (ref "A1") (pin "CN10_16") (pinfunction "D0/USART_A_RX_CN10_16") (pintype "input"))
    )
    (net (code "217") (name "unconnected-(A1F-D1{slash}USART_A_TX-PadCN10_14)") (class "Default")
      (node (ref "A1") (pin "CN10_14") (pinfunction "D1/USART_A_TX_CN10_14") (pintype "output"))
    )
    (net (code "218") (name "unconnected-(A1F-D2{slash}IO-PadCN10_12)") (class "Default")
      (node (ref "A1") (pin "CN10_12") (pinfunction "D2/IO_CN10_12") (pintype "bidirectional"))
    )
    (net (code "219") (name "unconnected-(A1F-D3{slash}TIMER_A_PWM3-PadCN10_10)") (class "Default")
      (node (ref "A1") (pin "CN10_10") (pinfunction "D3/TIMER_A_PWM3_CN10_10") (pintype "bidirectional"))
    )
    (net (code "220") (name "unconnected-(A1F-D4{slash}IO-PadCN10_8)") (class "Default")
      (node (ref "A1") (pin "CN10_8") (pinfunction "D4/IO_CN10_8") (pintype "bidirectional"))
    )
    (net (code "221") (name "unconnected-(A1F-D5{slash}TIMER_A_PWM2-PadCN10_6)") (class "Default")
      (node (ref "A1") (pin "CN10_6") (pinfunction "D5/TIMER_A_PWM2_CN10_6") (pintype "bidirectional"))
    )
    (net (code "222") (name "unconnected-(A1F-D6{slash}TIMER_A_PWM1-PadCN10_4)") (class "Default")
      (node (ref "A1") (pin "CN10_4") (pinfunction "D6/TIMER_A_PWM1_CN10_4") (pintype "bidirectional"))
    )
    (net (code "223") (name "unconnected-(A1F-D7{slash}IO-PadCN10_2)") (class "Default")
      (node (ref "A1") (pin "CN10_2") (pinfunction "D7/IO_CN10_2") (pintype "bidirectional"))
    )
    (net (code "224") (name "unconnected-(A1F-D26{slash}QSPI_CS-PadCN10_13)") (class "Default")
      (node (ref "A1") (pin "CN10_13") (pinfunction "D26/QSPI_CS_CN10_13") (pintype "bidirectional"))
    )
    (net (code "225") (name "unconnected-(A1F-D27{slash}QSPI_CLK-PadCN10_15)") (class "Default")
      (node (ref "A1") (pin "CN10_15") (pinfunction "D27/QSPI_CLK_CN10_15") (pintype "bidirectional"))
    )
    (net (code "226") (name "unconnected-(A1F-D28{slash}QSPI_BK1_IO3-PadCN10_19)") (class "Default")
      (node (ref "A1") (pin "CN10_19") (pinfunction "D28/QSPI_BK1_IO3_CN10_19") (pintype "bidirectional"))
    )
    (net (code "227") (name "unconnected-(A1F-D29{slash}QSPI_BK1_IO1-PadCN10_21)") (class "Default")
      (node (ref "A1") (pin "CN10_21") (pinfunction "D29/QSPI_BK1_IO1_CN10_21") (pintype "bidirectional"))
    )
    (net (code "228") (name "unconnected-(A1F-D30{slash}QSPI_BK1_IO0-PadCN10_23)") (class "Default")
      (node (ref "A1") (pin "CN10_23") (pinfunction "D30/QSPI_BK1_IO0_CN10_23") (pintype "bidirectional"))
    )
    (net (code "229") (name "unconnected-(A1F-D31{slash}QSPI_BK1_IO2-PadCN10_25)") (class "Default")
      (node (ref "A1") (pin "CN10_25") (pinfunction "D31/QSPI_BK1_IO2_CN10_25") (pintype "bidirectional"))
    )
    (net (code "230") (name "unconnected-(A1F-D32{slash}TIMER_C_PWM1-PadCN10_29)") (class "Default")
      (node (ref "A1") (pin "CN10_29") (pinfunction "D32/TIMER_C_PWM1_CN10_29") (pintype "bidirectional"))
    )
    (net (code "231") (name "unconnected-(A1F-D33{slash}TIMER_D_PWM1-PadCN10_31)") (class "Default")
      (node (ref "A1") (pin "CN10_31") (pinfunction "D33/TIMER_D_PWM1_CN10_31") (pintype "bidirectional"))
    )
    (net (code "232") (name "unconnected-(A1F-D34{slash}TIMER_B_ETR-PadCN10_33)") (class "Default")
      (node (ref "A1") (pin "CN10_33") (pinfunction "D34/TIMER_B_ETR_CN10_33") (pintype "bidirectional"))
    )
    (net (code "233") (name "unconnected-(A1F-D35{slash}TIMER_C_PWM3-PadCN10_34)") (class "Default")
      (node (ref "A1") (pin "CN10_34") (pinfunction "D35/TIMER_C_PWM3_CN10_34") (pintype "bidirectional"))
    )
    (net (code "234") (name "unconnected-(A1F-D36{slash}TIMER_C_PWM2-PadCN10_32)") (class "Default")
      (node (ref "A1") (pin "CN10_32") (pinfunction "D36/TIMER_C_PWM2_CN10_32") (pintype "bidirectional"))
    )
    (net (code "235") (name "unconnected-(A1F-D37{slash}TIMER_A_BKIN1-PadCN10_30)") (class "Default")
      (node (ref "A1") (pin "CN10_30") (pinfunction "D37/TIMER_A_BKIN1_CN10_30") (pintype "bidirectional"))
    )
    (net (code "236") (name "unconnected-(A1F-D38{slash}IO-PadCN10_28)") (class "Default")
      (node (ref "A1") (pin "CN10_28") (pinfunction "D38/IO_CN10_28") (pintype "bidirectional"))
    )
    (net (code "237") (name "unconnected-(A1F-D39{slash}TIMER_A_PWM3N-PadCN10_26)") (class "Default")
      (node (ref "A1") (pin "CN10_26") (pinfunction "D39/TIMER_A_PWM3N_CN10_26") (pintype "bidirectional"))
    )
    (net (code "238") (name "unconnected-(A1F-D40{slash}TIMER_A_PWM2N-PadCN10_24)") (class "Default")
      (node (ref "A1") (pin "CN10_24") (pinfunction "D40/TIMER_A_PWM2N_CN10_24") (pintype "bidirectional"))
    )
    (net (code "239") (name "unconnected-(A1F-D41{slash}TIMER_A_ETR-PadCN10_20)") (class "Default")
      (node (ref "A1") (pin "CN10_20") (pinfunction "D41/TIMER_A_ETR_CN10_20") (pintype "bidirectional"))
    )
    (net (code "240") (name "unconnected-(A1F-D42{slash}TIMER_A_PWM1N-PadCN10_18)") (class "Default")
      (node (ref "A1") (pin "CN10_18") (pinfunction "D42/TIMER_A_PWM1N_CN10_18") (pintype "bidirectional"))
    )
    (net (code "241") (name "unconnected-(J1-D+-Pad3)") (class "Default")
      (node (ref "J1") (pin "3") (pinfunction "D+_3") (pintype "bidirectional"))
    )
    (net (code "242") (name "unconnected-(J1-D--Pad2)") (class "Default")
      (node (ref "J1") (pin "2") (pinfunction "D-_2") (pintype "bidirectional"))
    )
    (net (code "243") (name "unconnected-(J1-ID-Pad4)") (class "Default")
      (node (ref "J1") (pin "4") (pinfunction "ID_4") (pintype "bidirectional"))
    )
  )
)
